# CANnode.net
KiCad netlist of a schematic drawn in Altium Designer
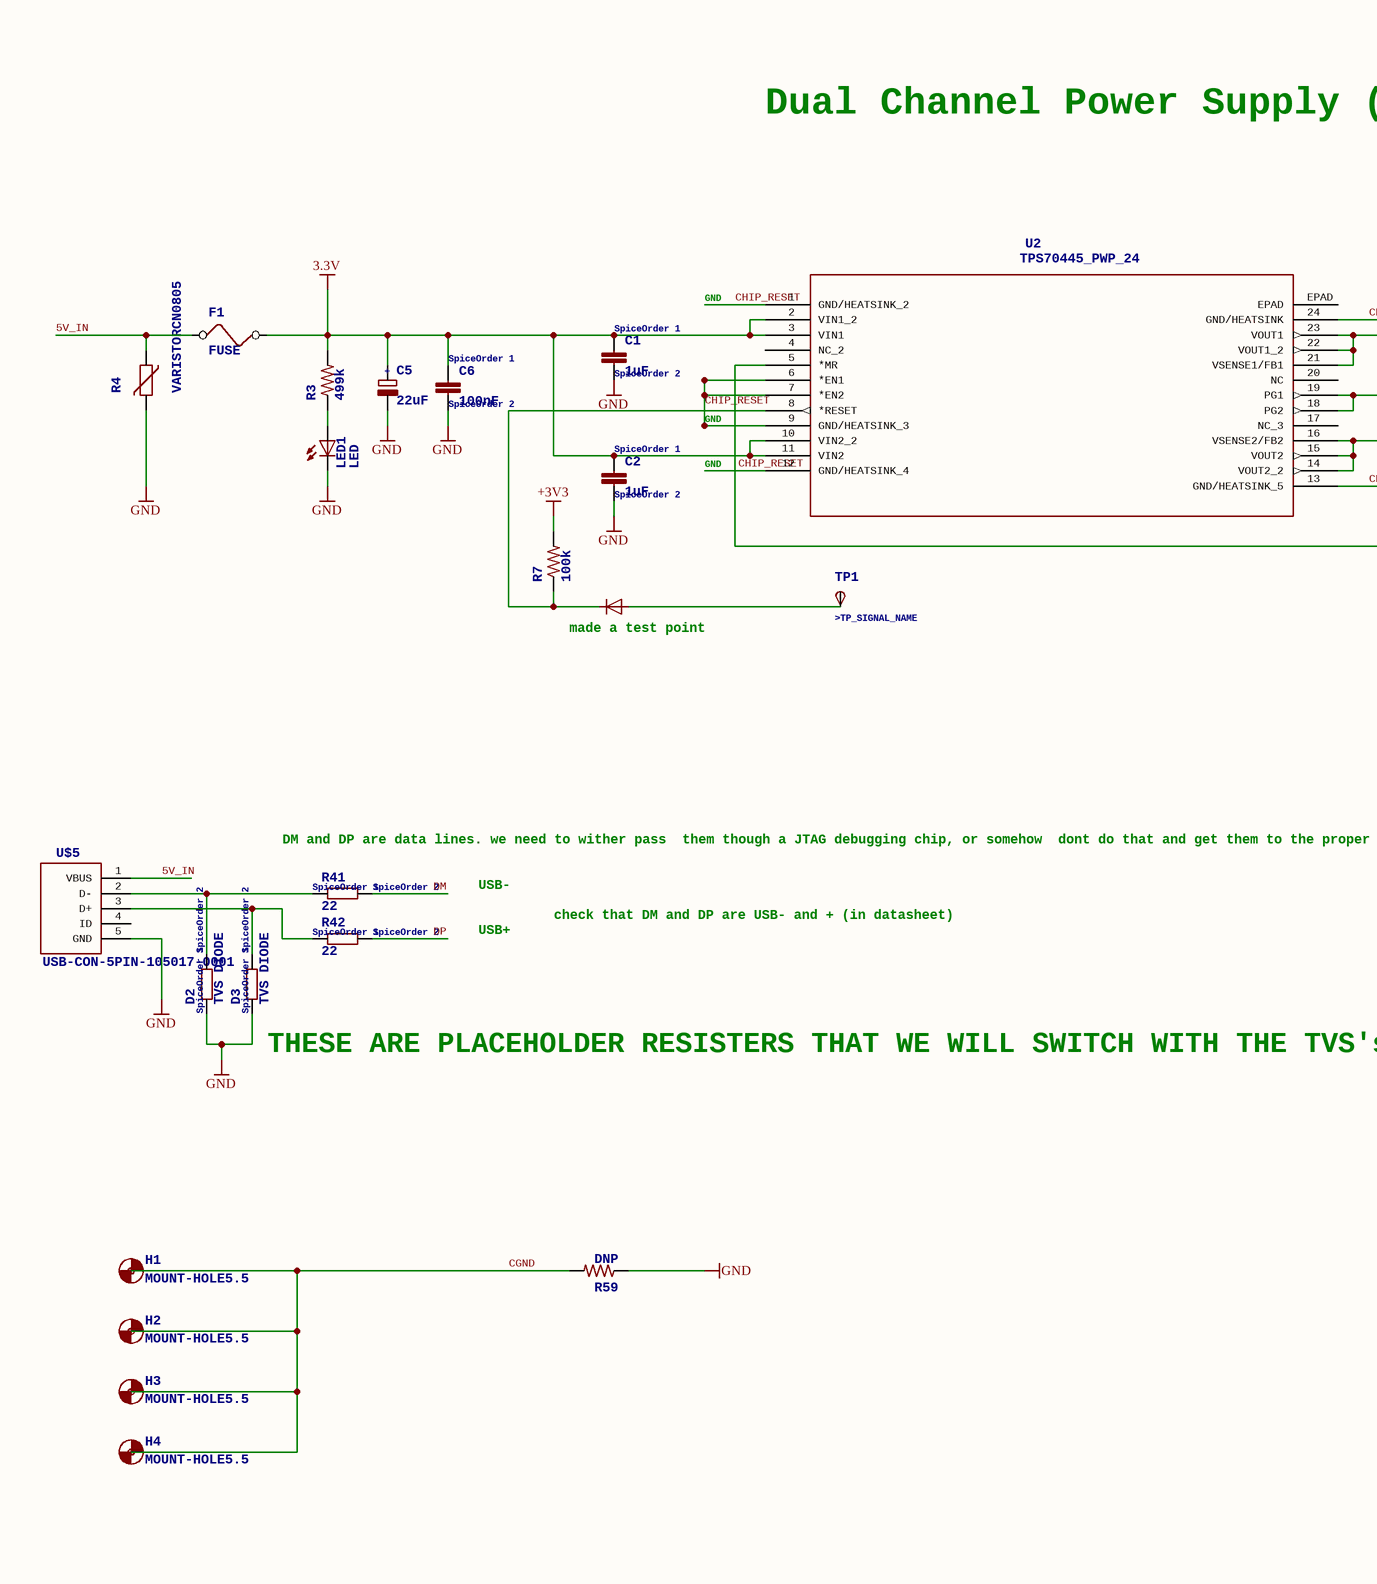
[diagram p0: CANnode.SchDoc, top left]
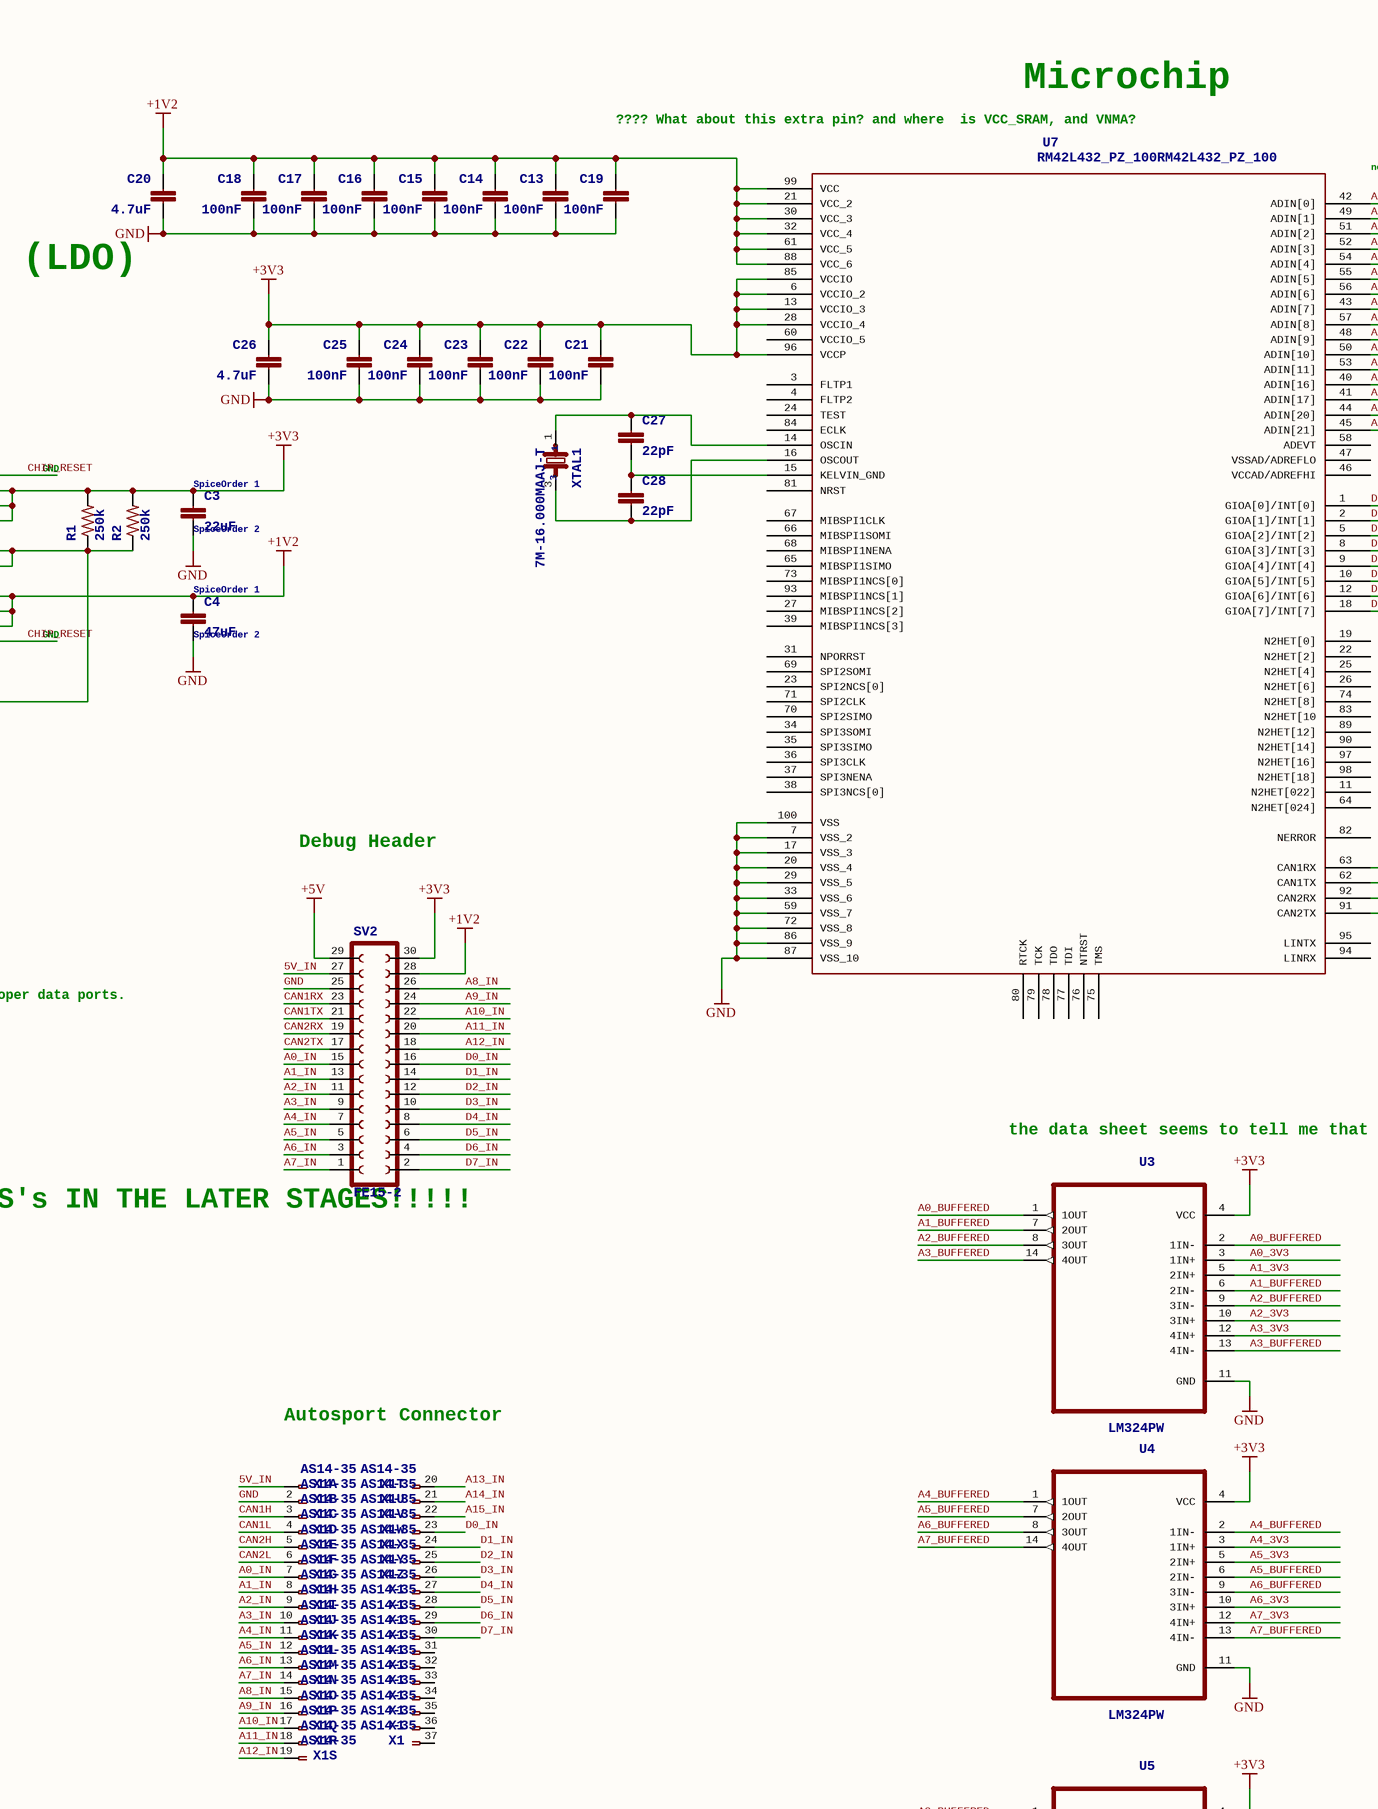
[diagram p1: CANnode.SchDoc, top middle]
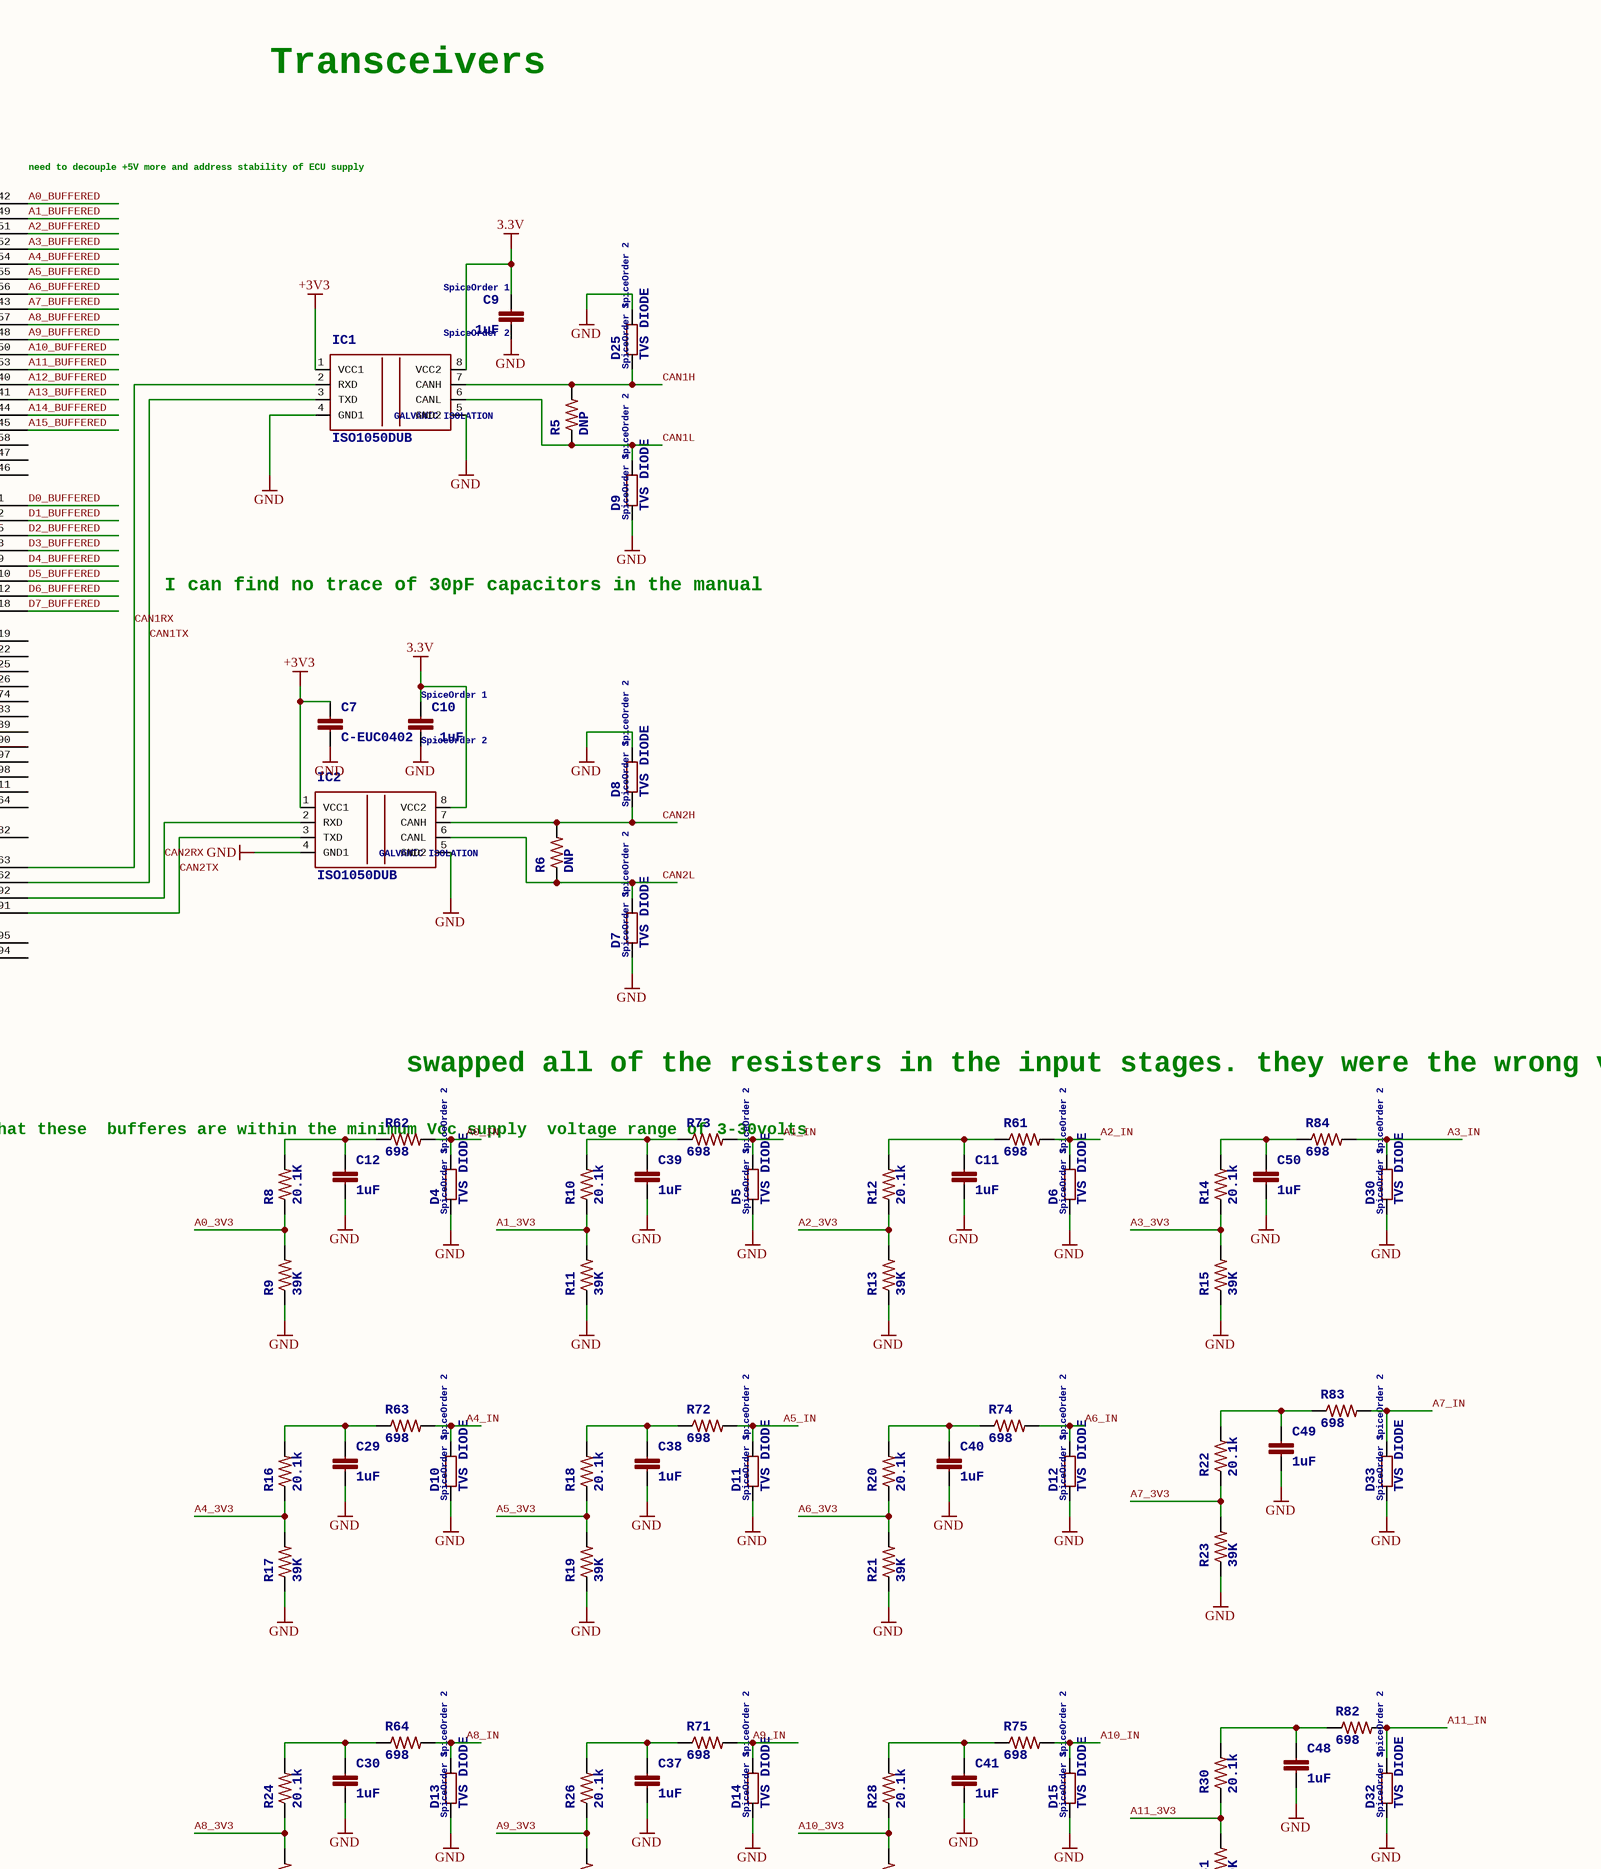
[diagram p2: CANnode.SchDoc, top right]
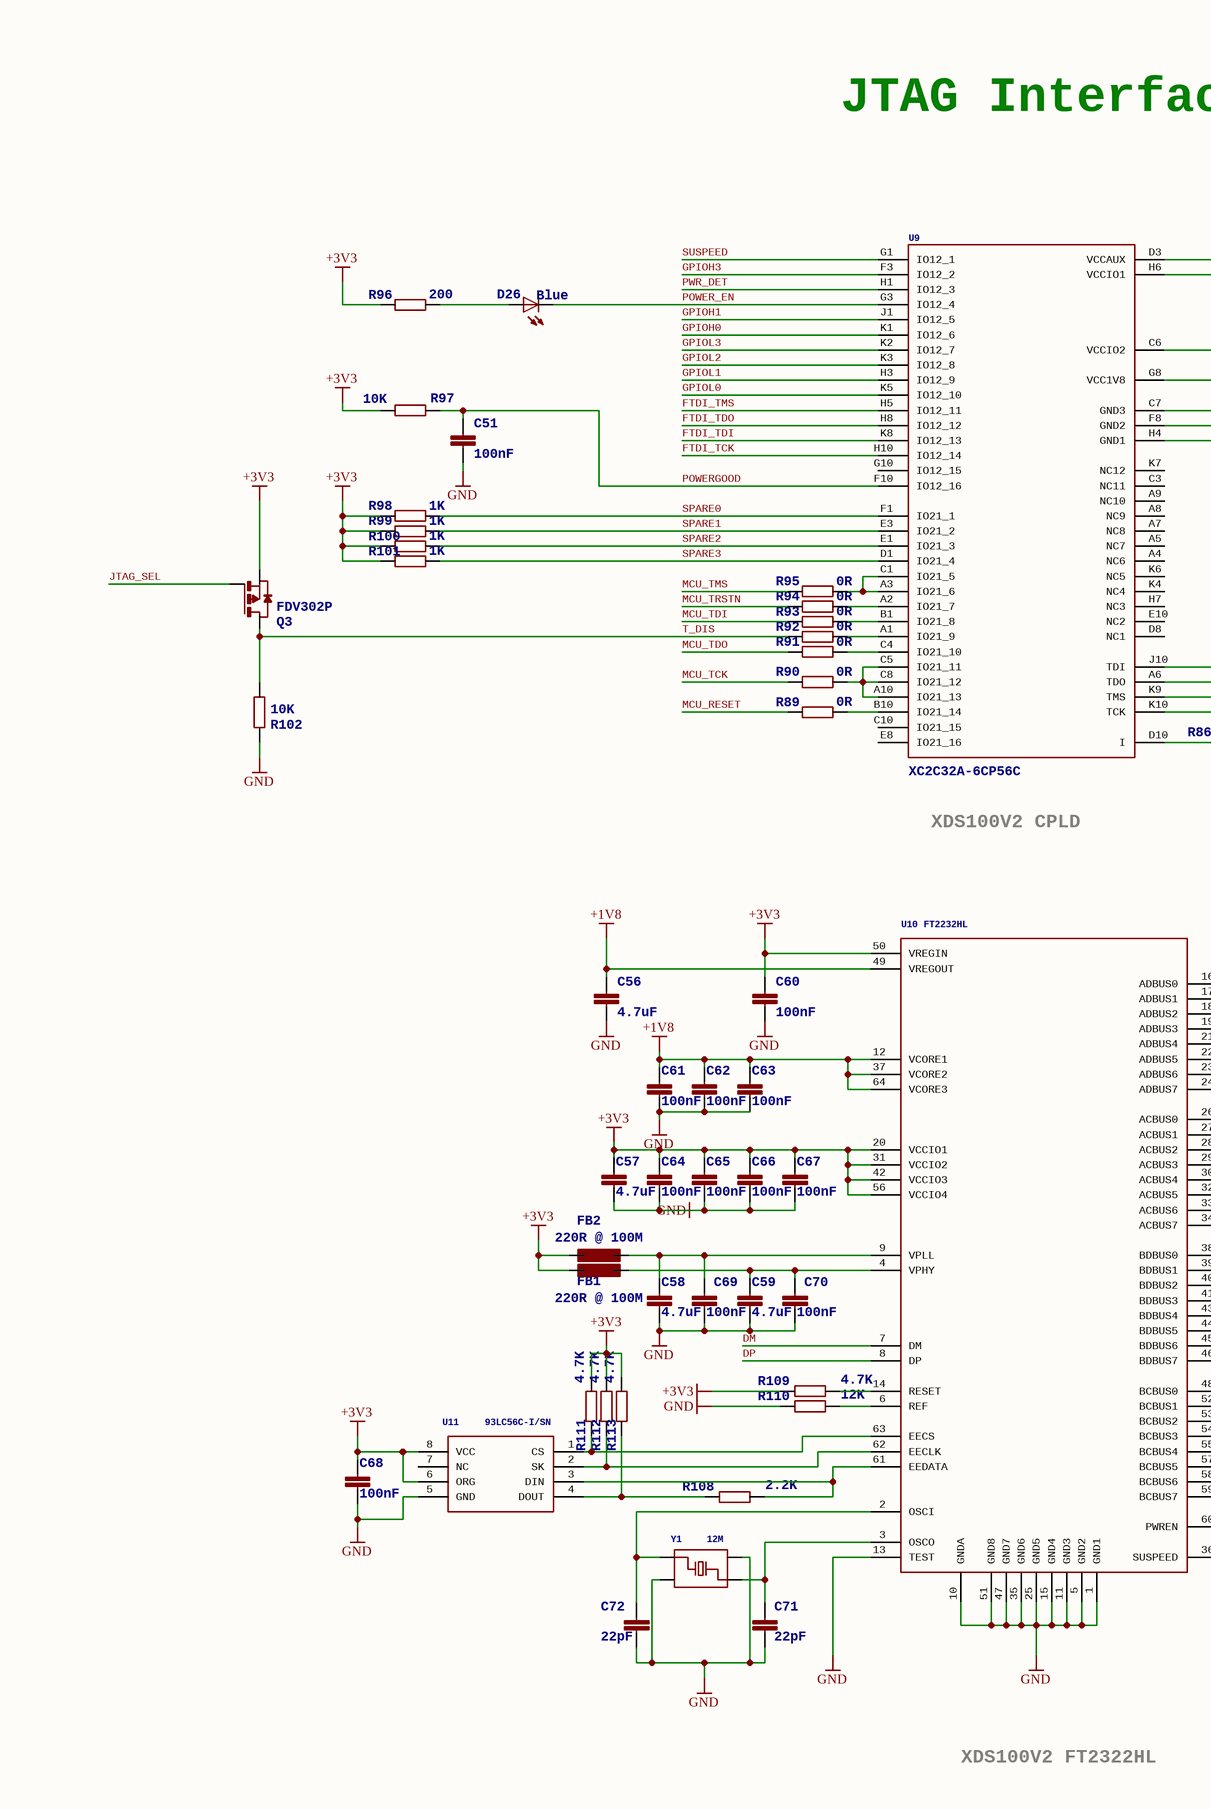
[diagram p3: CANnode.SchDoc, bottom left]
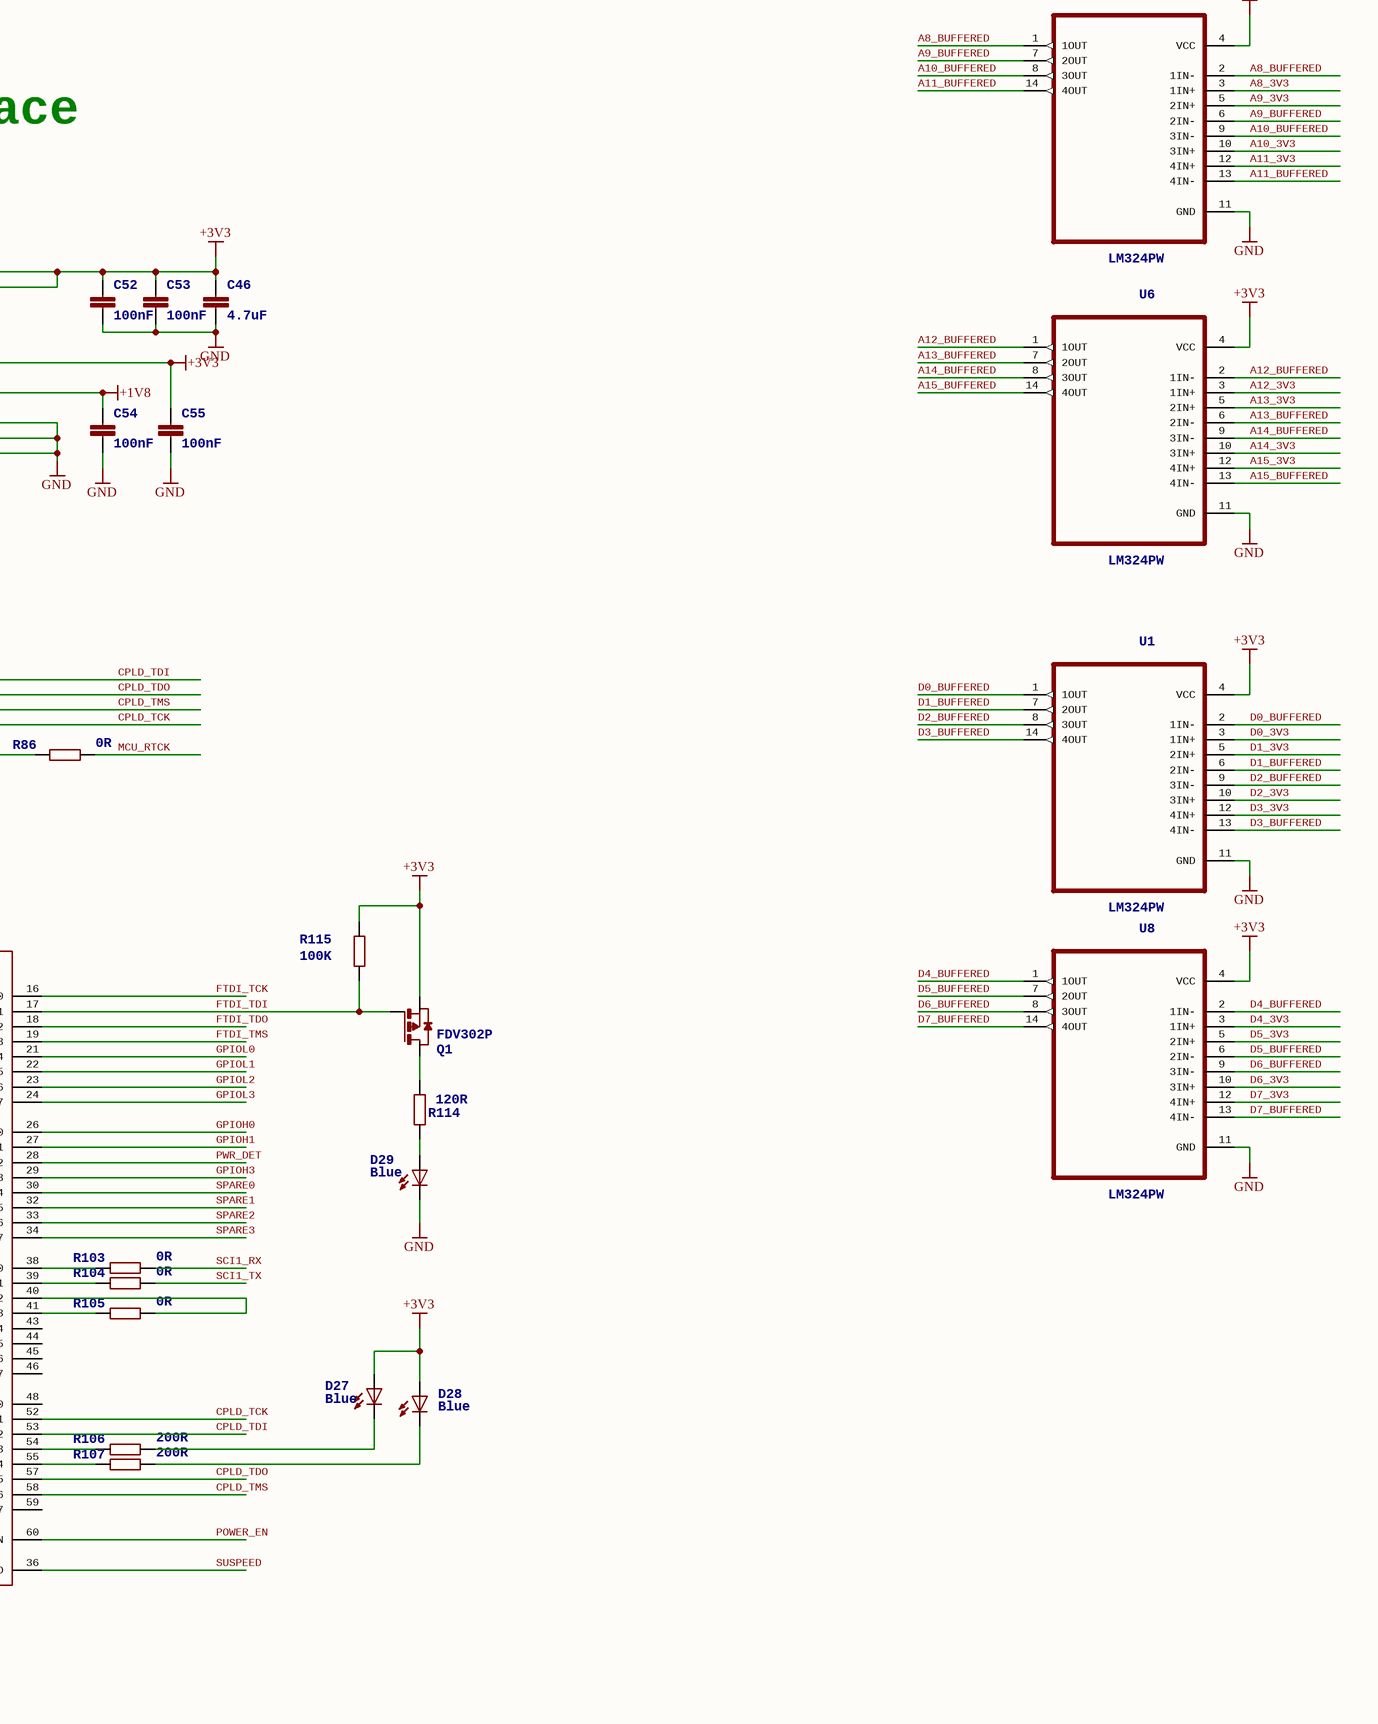
[diagram p4: CANnode.SchDoc, bottom middle]
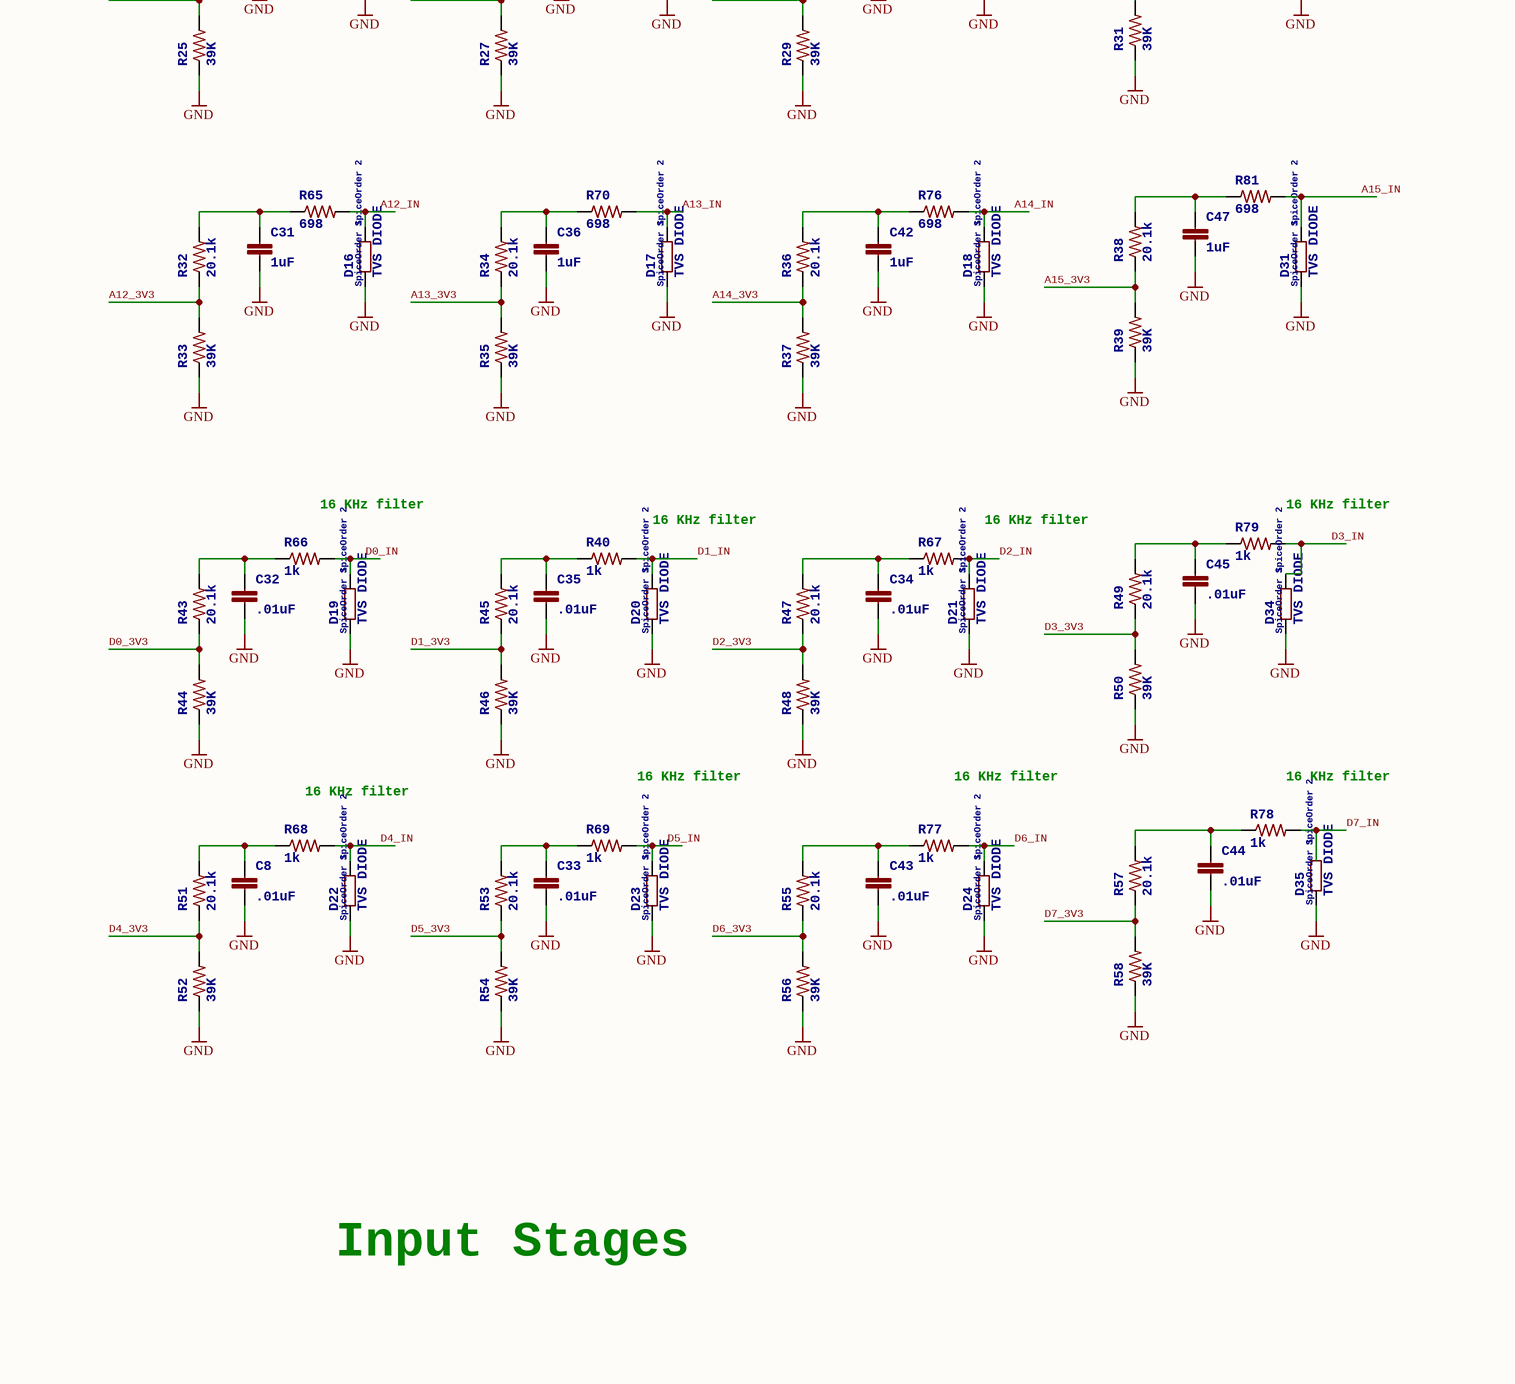
[diagram p5: CANnode.SchDoc, bottom right]

(export (version "E")
  (design (tool "Eeschema 10.0.6"))
  (components
    (comp (ref "C1")
      (value "1uF")
      (footprint "C0402")
      (description "<B>CAPACITOR</B>, European symbol")
      (fields (field (name "SPICEORDER 1") "SpiceOrder 1") (field (name "SPICEORDER 2") "SpiceOrder 2"))
      (libsource (lib "eagle-ltspice") (part "CC0402"))
    )
    (comp (ref "C2")
      (value "1uF")
      (footprint "C0402")
      (description "<B>CAPACITOR</B>, European symbol")
      (fields (field (name "SPICEORDER 1") "SpiceOrder 1") (field (name "SPICEORDER 2") "SpiceOrder 2"))
      (libsource (lib "eagle-ltspice") (part "CC0402"))
    )
    (comp (ref "C3")
      (value "22uF")
      (footprint "C0402")
      (description "<B>CAPACITOR</B>, European symbol")
      (fields (field (name "SPICEORDER 1") "SpiceOrder 1") (field (name "SPICEORDER 2") "SpiceOrder 2"))
      (libsource (lib "eagle-ltspice") (part "CC0402"))
    )
    (comp (ref "C4")
      (value "47uF")
      (footprint "C0402")
      (description "<B>CAPACITOR</B>, European symbol")
      (fields (field (name "SPICEORDER 1") "SpiceOrder 1") (field (name "SPICEORDER 2") "SpiceOrder 2"))
      (libsource (lib "eagle-ltspice") (part "CC0402"))
    )
    (comp (ref "C5")
      (value "22uF")
      (footprint "CT3528")
      (description "<B>POLARIZED CAPACITOR</B>, European symbol")
      (fields (field (name "+") "+"))
      (libsource (lib "resistor") (part "CPOL-EUCT3528"))
    )
    (comp (ref "C6")
      (value "100nF")
      (footprint "C0402")
      (description "<B>CAPACITOR</B>, European symbol")
      (fields (field (name "SPICEORDER 1") "SpiceOrder 1") (field (name "SPICEORDER 2") "SpiceOrder 2"))
      (libsource (lib "eagle-ltspice") (part "CC0402"))
    )
    (comp (ref "C7")
      (value "C-EUC0402")
      (footprint "C0402")
      (description "<B>CAPACITOR</B>, European symbol")
      (libsource (lib "") (part "C-EUC0402_1"))
    )
    (comp (ref "C8")
      (value ".01uF")
      (footprint "C0402")
      (description "<B>CAPACITOR</B>, European symbol")
      (libsource (lib "") (part "C-EUC0402_1"))
    )
    (comp (ref "C9")
      (value ".1uF")
      (footprint "C0402")
      (description "<B>CAPACITOR</B>, European symbol")
      (fields (field (name "SPICEORDER 1") "SpiceOrder 1") (field (name "SPICEORDER 2") "SpiceOrder 2"))
      (libsource (lib "") (part "CC0402_1"))
    )
    (comp (ref "C10")
      (value ".1uF")
      (footprint "C0402")
      (description "<B>CAPACITOR</B>, European symbol")
      (fields (field (name "SPICEORDER 1") "SpiceOrder 1") (field (name "SPICEORDER 2") "SpiceOrder 2"))
      (libsource (lib "eagle-ltspice") (part "CC0402"))
    )
    (comp (ref "C11")
      (value "1uF")
      (footprint "C0402")
      (description "<B>CAPACITOR</B>, European symbol")
      (libsource (lib "") (part "C-EUC0402_1"))
    )
    (comp (ref "C12")
      (value "1uF")
      (footprint "C0402")
      (description "<B>CAPACITOR</B>, European symbol")
      (libsource (lib "") (part "C-EUC0402_1"))
    )
    (comp (ref "C13")
      (value "100nF")
      (footprint "C0402")
      (description "<B>CAPACITOR</B>, European symbol")
      (libsource (lib "rcl") (part "C-EUC0402"))
    )
    (comp (ref "C14")
      (value "100nF")
      (footprint "C0402")
      (description "<B>CAPACITOR</B>, European symbol")
      (libsource (lib "rcl") (part "C-EUC0402"))
    )
    (comp (ref "C15")
      (value "100nF")
      (footprint "C0402")
      (description "<B>CAPACITOR</B>, European symbol")
      (libsource (lib "rcl") (part "C-EUC0402"))
    )
    (comp (ref "C16")
      (value "100nF")
      (footprint "C0402")
      (description "<B>CAPACITOR</B>, European symbol")
      (libsource (lib "rcl") (part "C-EUC0402"))
    )
    (comp (ref "C17")
      (value "100nF")
      (footprint "C0402")
      (description "<B>CAPACITOR</B>, European symbol")
      (libsource (lib "rcl") (part "C-EUC0402"))
    )
    (comp (ref "C18")
      (value "100nF")
      (footprint "C0402")
      (description "<B>CAPACITOR</B>, European symbol")
      (libsource (lib "rcl") (part "C-EUC0402"))
    )
    (comp (ref "C19")
      (value "100nF")
      (footprint "C0402")
      (description "<B>CAPACITOR</B>, European symbol")
      (libsource (lib "rcl") (part "C-EUC0402"))
    )
    (comp (ref "C20")
      (value "4.7uF")
      (footprint "C0805")
      (description "<B>CAPACITOR</B>, European symbol")
      (libsource (lib "rcl") (part "C-EUC0805"))
    )
    (comp (ref "C21")
      (value "100nF")
      (footprint "C0402")
      (description "<B>CAPACITOR</B>, European symbol")
      (libsource (lib "rcl") (part "C-EUC0402"))
    )
    (comp (ref "C22")
      (value "100nF")
      (footprint "C0402")
      (description "<B>CAPACITOR</B>, European symbol")
      (libsource (lib "rcl") (part "C-EUC0402"))
    )
    (comp (ref "C23")
      (value "100nF")
      (footprint "C0402")
      (description "<B>CAPACITOR</B>, European symbol")
      (libsource (lib "rcl") (part "C-EUC0402"))
    )
    (comp (ref "C24")
      (value "100nF")
      (footprint "C0402")
      (description "<B>CAPACITOR</B>, European symbol")
      (libsource (lib "rcl") (part "C-EUC0402"))
    )
    (comp (ref "C25")
      (value "100nF")
      (footprint "C0402")
      (description "<B>CAPACITOR</B>, European symbol")
      (libsource (lib "rcl") (part "C-EUC0402"))
    )
    (comp (ref "C26")
      (value "4.7uF")
      (footprint "C0805")
      (description "<B>CAPACITOR</B>, European symbol")
      (libsource (lib "rcl") (part "C-EUC0805"))
    )
    (comp (ref "C27")
      (value "22pF")
      (footprint "C0402")
      (description "<B>CAPACITOR</B>, European symbol")
      (libsource (lib "") (part "C-EUC0402_1"))
    )
    (comp (ref "C28")
      (value "22pF")
      (footprint "C0402")
      (description "<B>CAPACITOR</B>, European symbol")
      (libsource (lib "") (part "C-EUC0402_1"))
    )
    (comp (ref "C29")
      (value "1uF")
      (footprint "C0402")
      (description "<B>CAPACITOR</B>, European symbol")
      (libsource (lib "") (part "C-EUC0402_1"))
    )
    (comp (ref "C30")
      (value "1uF")
      (footprint "C0402")
      (description "<B>CAPACITOR</B>, European symbol")
      (libsource (lib "") (part "C-EUC0402_1"))
    )
    (comp (ref "C31")
      (value "1uF")
      (footprint "C0402")
      (description "<B>CAPACITOR</B>, European symbol")
      (libsource (lib "") (part "C-EUC0402_1"))
    )
    (comp (ref "C32")
      (value ".01uF")
      (footprint "C0402")
      (description "<B>CAPACITOR</B>, European symbol")
      (libsource (lib "") (part "C-EUC0402_1"))
    )
    (comp (ref "C33")
      (value ".01uF")
      (footprint "C0402")
      (description "<B>CAPACITOR</B>, European symbol")
      (libsource (lib "") (part "C-EUC0402_1"))
    )
    (comp (ref "C34")
      (value ".01uF")
      (footprint "C0402")
      (description "<B>CAPACITOR</B>, European symbol")
      (libsource (lib "") (part "C-EUC0402_1"))
    )
    (comp (ref "C35")
      (value ".01uF")
      (footprint "C0402")
      (description "<B>CAPACITOR</B>, European symbol")
      (libsource (lib "") (part "C-EUC0402_1"))
    )
    (comp (ref "C36")
      (value "1uF")
      (footprint "C0402")
      (description "<B>CAPACITOR</B>, European symbol")
      (libsource (lib "") (part "C-EUC0402_1"))
    )
    (comp (ref "C37")
      (value "1uF")
      (footprint "C0402")
      (description "<B>CAPACITOR</B>, European symbol")
      (libsource (lib "") (part "C-EUC0402_1"))
    )
    (comp (ref "C38")
      (value "1uF")
      (footprint "C0402")
      (description "<B>CAPACITOR</B>, European symbol")
      (libsource (lib "") (part "C-EUC0402_1"))
    )
    (comp (ref "C39")
      (value "1uF")
      (footprint "C0402")
      (description "<B>CAPACITOR</B>, European symbol")
      (libsource (lib "") (part "C-EUC0402_1"))
    )
    (comp (ref "C40")
      (value "1uF")
      (footprint "C0402")
      (description "<B>CAPACITOR</B>, European symbol")
      (libsource (lib "") (part "C-EUC0402_1"))
    )
    (comp (ref "C41")
      (value "1uF")
      (footprint "C0402")
      (description "<B>CAPACITOR</B>, European symbol")
      (libsource (lib "") (part "C-EUC0402_1"))
    )
    (comp (ref "C42")
      (value "1uF")
      (footprint "C0402")
      (description "<B>CAPACITOR</B>, European symbol")
      (libsource (lib "") (part "C-EUC0402_1"))
    )
    (comp (ref "C43")
      (value ".01uF")
      (footprint "C0402")
      (description "<B>CAPACITOR</B>, European symbol")
      (libsource (lib "") (part "C-EUC0402_1"))
    )
    (comp (ref "C44")
      (value ".01uF")
      (footprint "C0402")
      (description "<B>CAPACITOR</B>, European symbol")
      (libsource (lib "") (part "C-EUC0402_1"))
    )
    (comp (ref "C45")
      (value ".01uF")
      (footprint "C0402")
      (description "<B>CAPACITOR</B>, European symbol")
      (libsource (lib "") (part "C-EUC0402_1"))
    )
    (comp (ref "C46") (value "4.7uF") (footprint "0805") (libsource (lib "launchpad") (part "CAP0805")))
    (comp (ref "C47")
      (value "1uF")
      (footprint "C0402")
      (description "<B>CAPACITOR</B>, European symbol")
      (libsource (lib "") (part "C-EUC0402_1"))
    )
    (comp (ref "C48")
      (value "1uF")
      (footprint "C0402")
      (description "<B>CAPACITOR</B>, European symbol")
      (libsource (lib "") (part "C-EUC0402_1"))
    )
    (comp (ref "C49")
      (value "1uF")
      (footprint "C0402")
      (description "<B>CAPACITOR</B>, European symbol")
      (libsource (lib "") (part "C-EUC0402_1"))
    )
    (comp (ref "C50")
      (value "1uF")
      (footprint "C0402")
      (description "<B>CAPACITOR</B>, European symbol")
      (libsource (lib "") (part "C-EUC0402_1"))
    )
    (comp (ref "C51") (value "100nF") (footprint "0402") (libsource (lib "launchpad") (part "CAP0402")))
    (comp (ref "C52") (value "100nF") (footprint "0402") (libsource (lib "launchpad") (part "CAP0402")))
    (comp (ref "C53") (value "100nF") (footprint "0402") (libsource (lib "launchpad") (part "CAP0402")))
    (comp (ref "C54") (value "100nF") (footprint "0402") (libsource (lib "launchpad") (part "CAP0402")))
    (comp (ref "C55") (value "100nF") (footprint "0402") (libsource (lib "launchpad") (part "CAP0402")))
    (comp (ref "C56") (value "4.7uF") (footprint "0805") (libsource (lib "launchpad") (part "CAP0805")))
    (comp (ref "C57") (value "4.7uF") (footprint "0805") (libsource (lib "launchpad") (part "CAP0805")))
    (comp (ref "C58") (value "4.7uF") (footprint "0805") (libsource (lib "launchpad") (part "CAP0805")))
    (comp (ref "C59") (value "4.7uF") (footprint "0805") (libsource (lib "launchpad") (part "CAP0805")))
    (comp (ref "C60") (value "100nF") (footprint "0402") (libsource (lib "launchpad") (part "CAP0402")))
    (comp (ref "C61") (value "100nF") (footprint "0402") (libsource (lib "launchpad") (part "CAP0402")))
    (comp (ref "C62") (value "100nF") (footprint "0402") (libsource (lib "launchpad") (part "CAP0402")))
    (comp (ref "C63") (value "100nF") (footprint "0402") (libsource (lib "launchpad") (part "CAP0402")))
    (comp (ref "C64") (value "100nF") (footprint "0402") (libsource (lib "launchpad") (part "CAP0402")))
    (comp (ref "C65") (value "100nF") (footprint "0402") (libsource (lib "launchpad") (part "CAP0402")))
    (comp (ref "C66") (value "100nF") (footprint "0402") (libsource (lib "launchpad") (part "CAP0402")))
    (comp (ref "C67") (value "100nF") (footprint "0402") (libsource (lib "launchpad") (part "CAP0402")))
    (comp (ref "C68") (value "100nF") (footprint "0402") (libsource (lib "launchpad") (part "CAP0402")))
    (comp (ref "C69") (value "100nF") (footprint "0402") (libsource (lib "launchpad") (part "CAP0402")))
    (comp (ref "C70") (value "100nF") (footprint "0402") (libsource (lib "launchpad") (part "CAP0402")))
    (comp (ref "C71") (value "22pF") (footprint "0402") (libsource (lib "launchpad") (part "CAP0402")))
    (comp (ref "C72") (value "22pF") (footprint "0402") (libsource (lib "launchpad") (part "CAP0402")))
    (comp (ref "D1")
      (value "DIODE")
      (description "<B>DIODE</B><p>")
      (libsource (lib "docu-dummy") (part "DIODE"))
    )
    (comp (ref "D2")
      (value "TVS DIODE")
      (footprint "R0402")
      (description "<B>RESISTOR</B>, European symbol")
      (fields (field (name "SPICEORDER 1") "SpiceOrder 1") (field (name "SPICEORDER 2") "SpiceOrder 2"))
      (libsource (lib "eagle-ltspice") (part "RR0402"))
    )
    (comp (ref "D3")
      (value "TVS DIODE")
      (footprint "R0402")
      (description "<B>RESISTOR</B>, European symbol")
      (fields (field (name "SPICEORDER 1") "SpiceOrder 1") (field (name "SPICEORDER 2") "SpiceOrder 2"))
      (libsource (lib "eagle-ltspice") (part "RR0402"))
    )
    (comp (ref "D4")
      (value "TVS DIODE")
      (footprint "R0402")
      (description "<B>RESISTOR</B>, European symbol")
      (fields (field (name "SPICEORDER 1") "SpiceOrder 1") (field (name "SPICEORDER 2") "SpiceOrder 2"))
      (libsource (lib "eagle-ltspice") (part "RR0402"))
    )
    (comp (ref "D5")
      (value "TVS DIODE")
      (footprint "R0402")
      (description "<B>RESISTOR</B>, European symbol")
      (fields (field (name "SPICEORDER 1") "SpiceOrder 1") (field (name "SPICEORDER 2") "SpiceOrder 2"))
      (libsource (lib "eagle-ltspice") (part "RR0402"))
    )
    (comp (ref "D6")
      (value "TVS DIODE")
      (footprint "R0402")
      (description "<B>RESISTOR</B>, European symbol")
      (fields (field (name "SPICEORDER 1") "SpiceOrder 1") (field (name "SPICEORDER 2") "SpiceOrder 2"))
      (libsource (lib "eagle-ltspice") (part "RR0402"))
    )
    (comp (ref "D7")
      (value "TVS DIODE")
      (footprint "R0402")
      (description "<B>RESISTOR</B>, European symbol")
      (fields (field (name "SPICEORDER 1") "SpiceOrder 1") (field (name "SPICEORDER 2") "SpiceOrder 2"))
      (libsource (lib "eagle-ltspice") (part "RR0402"))
    )
    (comp (ref "D8")
      (value "TVS DIODE")
      (footprint "R0402")
      (description "<B>RESISTOR</B>, European symbol")
      (fields (field (name "SPICEORDER 1") "SpiceOrder 1") (field (name "SPICEORDER 2") "SpiceOrder 2"))
      (libsource (lib "eagle-ltspice") (part "RR0402"))
    )
    (comp (ref "D9")
      (value "TVS DIODE")
      (footprint "R0402")
      (description "<B>RESISTOR</B>, European symbol")
      (fields (field (name "SPICEORDER 1") "SpiceOrder 1") (field (name "SPICEORDER 2") "SpiceOrder 2"))
      (libsource (lib "eagle-ltspice") (part "RR0402"))
    )
    (comp (ref "D10")
      (value "TVS DIODE")
      (footprint "R0402")
      (description "<B>RESISTOR</B>, European symbol")
      (fields (field (name "SPICEORDER 1") "SpiceOrder 1") (field (name "SPICEORDER 2") "SpiceOrder 2"))
      (libsource (lib "eagle-ltspice") (part "RR0402"))
    )
    (comp (ref "D11")
      (value "TVS DIODE")
      (footprint "R0402")
      (description "<B>RESISTOR</B>, European symbol")
      (fields (field (name "SPICEORDER 1") "SpiceOrder 1") (field (name "SPICEORDER 2") "SpiceOrder 2"))
      (libsource (lib "eagle-ltspice") (part "RR0402"))
    )
    (comp (ref "D12")
      (value "TVS DIODE")
      (footprint "R0402")
      (description "<B>RESISTOR</B>, European symbol")
      (fields (field (name "SPICEORDER 1") "SpiceOrder 1") (field (name "SPICEORDER 2") "SpiceOrder 2"))
      (libsource (lib "eagle-ltspice") (part "RR0402"))
    )
    (comp (ref "D13")
      (value "TVS DIODE")
      (footprint "R0402")
      (description "<B>RESISTOR</B>, European symbol")
      (fields (field (name "SPICEORDER 1") "SpiceOrder 1") (field (name "SPICEORDER 2") "SpiceOrder 2"))
      (libsource (lib "eagle-ltspice") (part "RR0402"))
    )
    (comp (ref "D14")
      (value "TVS DIODE")
      (footprint "R0402")
      (description "<B>RESISTOR</B>, European symbol")
      (fields (field (name "SPICEORDER 1") "SpiceOrder 1") (field (name "SPICEORDER 2") "SpiceOrder 2"))
      (libsource (lib "eagle-ltspice") (part "RR0402"))
    )
    (comp (ref "D15")
      (value "TVS DIODE")
      (footprint "R0402")
      (description "<B>RESISTOR</B>, European symbol")
      (fields (field (name "SPICEORDER 1") "SpiceOrder 1") (field (name "SPICEORDER 2") "SpiceOrder 2"))
      (libsource (lib "eagle-ltspice") (part "RR0402"))
    )
    (comp (ref "D16")
      (value "TVS DIODE")
      (footprint "R0402")
      (description "<B>RESISTOR</B>, European symbol")
      (fields (field (name "SPICEORDER 1") "SpiceOrder 1") (field (name "SPICEORDER 2") "SpiceOrder 2"))
      (libsource (lib "eagle-ltspice") (part "RR0402"))
    )
    (comp (ref "D17")
      (value "TVS DIODE")
      (footprint "R0402")
      (description "<B>RESISTOR</B>, European symbol")
      (fields (field (name "SPICEORDER 1") "SpiceOrder 1") (field (name "SPICEORDER 2") "SpiceOrder 2"))
      (libsource (lib "eagle-ltspice") (part "RR0402"))
    )
    (comp (ref "D18")
      (value "TVS DIODE")
      (footprint "R0402")
      (description "<B>RESISTOR</B>, European symbol")
      (fields (field (name "SPICEORDER 1") "SpiceOrder 1") (field (name "SPICEORDER 2") "SpiceOrder 2"))
      (libsource (lib "eagle-ltspice") (part "RR0402"))
    )
    (comp (ref "D19")
      (value "TVS DIODE")
      (footprint "R0402")
      (description "<B>RESISTOR</B>, European symbol")
      (fields (field (name "SPICEORDER 1") "SpiceOrder 1") (field (name "SPICEORDER 2") "SpiceOrder 2"))
      (libsource (lib "eagle-ltspice") (part "RR0402"))
    )
    (comp (ref "D20")
      (value "TVS DIODE")
      (footprint "R0402")
      (description "<B>RESISTOR</B>, European symbol")
      (fields (field (name "SPICEORDER 1") "SpiceOrder 1") (field (name "SPICEORDER 2") "SpiceOrder 2"))
      (libsource (lib "eagle-ltspice") (part "RR0402"))
    )
    (comp (ref "D21")
      (value "TVS DIODE")
      (footprint "R0402")
      (description "<B>RESISTOR</B>, European symbol")
      (fields (field (name "SPICEORDER 1") "SpiceOrder 1") (field (name "SPICEORDER 2") "SpiceOrder 2"))
      (libsource (lib "eagle-ltspice") (part "RR0402"))
    )
    (comp (ref "D22")
      (value "TVS DIODE")
      (footprint "R0402")
      (description "<B>RESISTOR</B>, European symbol")
      (fields (field (name "SPICEORDER 1") "SpiceOrder 1") (field (name "SPICEORDER 2") "SpiceOrder 2"))
      (libsource (lib "eagle-ltspice") (part "RR0402"))
    )
    (comp (ref "D23")
      (value "TVS DIODE")
      (footprint "R0402")
      (description "<B>RESISTOR</B>, European symbol")
      (fields (field (name "SPICEORDER 1") "SpiceOrder 1") (field (name "SPICEORDER 2") "SpiceOrder 2"))
      (libsource (lib "eagle-ltspice") (part "RR0402"))
    )
    (comp (ref "D24")
      (value "TVS DIODE")
      (footprint "R0402")
      (description "<B>RESISTOR</B>, European symbol")
      (fields (field (name "SPICEORDER 1") "SpiceOrder 1") (field (name "SPICEORDER 2") "SpiceOrder 2"))
      (libsource (lib "eagle-ltspice") (part "RR0402"))
    )
    (comp (ref "D25")
      (value "TVS DIODE")
      (footprint "R0402")
      (description "<B>RESISTOR</B>, European symbol")
      (fields (field (name "SPICEORDER 1") "SpiceOrder 1") (field (name "SPICEORDER 2") "SpiceOrder 2"))
      (libsource (lib "eagle-ltspice") (part "RR0402"))
    )
    (comp (ref "D26") (value "Blue") (footprint "LED0805") (libsource (lib "launchpad") (part "CHIP-LED")))
    (comp (ref "D27") (value "Blue") (footprint "LED0805") (libsource (lib "launchpad") (part "CHIP-LED")))
    (comp (ref "D28") (value "Blue") (footprint "LED0805") (libsource (lib "launchpad") (part "CHIP-LED")))
    (comp (ref "D29") (value "Blue") (footprint "LED0805") (libsource (lib "launchpad") (part "CHIP-LED")))
    (comp (ref "D30")
      (value "TVS DIODE")
      (footprint "R0402")
      (description "<B>RESISTOR</B>, European symbol")
      (fields (field (name "SPICEORDER 1") "SpiceOrder 1") (field (name "SPICEORDER 2") "SpiceOrder 2"))
      (libsource (lib "eagle-ltspice") (part "RR0402"))
    )
    (comp (ref "D31")
      (value "TVS DIODE")
      (footprint "R0402")
      (description "<B>RESISTOR</B>, European symbol")
      (fields (field (name "SPICEORDER 1") "SpiceOrder 1") (field (name "SPICEORDER 2") "SpiceOrder 2"))
      (libsource (lib "eagle-ltspice") (part "RR0402"))
    )
    (comp (ref "D32")
      (value "TVS DIODE")
      (footprint "R0402")
      (description "<B>RESISTOR</B>, European symbol")
      (fields (field (name "SPICEORDER 1") "SpiceOrder 1") (field (name "SPICEORDER 2") "SpiceOrder 2"))
      (libsource (lib "eagle-ltspice") (part "RR0402"))
    )
    (comp (ref "D33")
      (value "TVS DIODE")
      (footprint "R0402")
      (description "<B>RESISTOR</B>, European symbol")
      (fields (field (name "SPICEORDER 1") "SpiceOrder 1") (field (name "SPICEORDER 2") "SpiceOrder 2"))
      (libsource (lib "eagle-ltspice") (part "RR0402"))
    )
    (comp (ref "D34")
      (value "TVS DIODE")
      (footprint "R0402")
      (description "<B>RESISTOR</B>, European symbol")
      (fields (field (name "SPICEORDER 1") "SpiceOrder 1") (field (name "SPICEORDER 2") "SpiceOrder 2"))
      (libsource (lib "eagle-ltspice") (part "RR0402"))
    )
    (comp (ref "D35")
      (value "TVS DIODE")
      (footprint "R0402")
      (description "<B>RESISTOR</B>, European symbol")
      (fields (field (name "SPICEORDER 1") "SpiceOrder 1") (field (name "SPICEORDER 2") "SpiceOrder 2"))
      (libsource (lib "eagle-ltspice") (part "RR0402"))
    )
    (comp (ref "F1")
      (value "FUSE")
      (footprint "FUSE")
      (description "<B>FUSE</B><p>\n5 x 20 mm")
      (libsource (lib "special") (part "FUSE"))
    )
    (comp (ref "FB1")
      (value "220R @ 100M")
      (footprint "0805")
      (libsource (lib "launchpad") (part "INDUCTOR"))
    )
    (comp (ref "FB2")
      (value "220R @ 100M")
      (footprint "0805")
      (libsource (lib "launchpad") (part "INDUCTOR"))
    )
    (comp (ref "H1")
      (value "MOUNT-HOLE5.5")
      (footprint "5,5")
      (description "<b>MOUNTING HOLE</b> with drill center marker")
      (libsource (lib "holes") (part "MOUNT-HOLE5.5"))
    )
    (comp (ref "H2")
      (value "MOUNT-HOLE5.5")
      (footprint "5,5")
      (description "<b>MOUNTING HOLE</b> with drill center marker")
      (libsource (lib "holes") (part "MOUNT-HOLE5.5"))
    )
    (comp (ref "H3")
      (value "MOUNT-HOLE5.5")
      (footprint "5,5")
      (description "<b>MOUNTING HOLE</b> with drill center marker")
      (libsource (lib "holes") (part "MOUNT-HOLE5.5"))
    )
    (comp (ref "H4")
      (value "MOUNT-HOLE5.5")
      (footprint "5,5")
      (description "<b>MOUNTING HOLE</b> with drill center marker")
      (libsource (lib "holes") (part "MOUNT-HOLE5.5"))
    )
    (comp (ref "IC1")
      (value "ISO1050DUB")
      (footprint "DUB-R-PDSO-G8")
      (description "<b>ISOLATED CAN TRANSCEIVER</b><p>\nSource: http://focus.ti.com/lit/ds/symlink/iso1050.pdf")
      (fields (field (name "MPN") "ISO1050DUBR") (field (name "GALVANIC ISOLATION") "GALVANIC ISOLATION"))
      (libsource (lib "texas") (part "ISO1050DUB"))
    )
    (comp (ref "IC2")
      (value "ISO1050DUB")
      (footprint "DUB-R-PDSO-G8")
      (description "<b>ISOLATED CAN TRANSCEIVER</b><p>\nSource: http://focus.ti.com/lit/ds/symlink/iso1050.pdf")
      (fields (field (name "MPN") "ISO1050DUBR") (field (name "GALVANIC ISOLATION") "GALVANIC ISOLATION"))
      (libsource (lib "texas") (part "ISO1050DUB"))
    )
    (comp (ref "LED1") (value "LED") (footprint "SMARTLED-TTW") (libsource (lib "led") (part "LED")))
    (comp (ref "Q1")
      (value "FDV302P")
      (footprint "SOT-23")
      (description "<b>MOS FET</b>")
      (libsource (lib "zetex") (part "PMOSSOT23"))
    )
    (comp (ref "Q3")
      (value "FDV302P")
      (footprint "SOT-23")
      (description "<b>MOS FET</b>")
      (libsource (lib "zetex") (part "PMOSSOT23"))
    )
    (comp (ref "R1")
      (value "250k")
      (footprint "R0402")
      (description "<B>RESISTOR</B>, American symbol")
      (libsource (lib "resistor") (part "R-US_R0402"))
    )
    (comp (ref "R2")
      (value "250k")
      (footprint "R0402")
      (description "<B>RESISTOR</B>, American symbol")
      (libsource (lib "resistor") (part "R-US_R0402"))
    )
    (comp (ref "R3")
      (value "499k")
      (footprint "R0402")
      (description "<B>RESISTOR</B>, American symbol")
      (libsource (lib "resistor") (part "R-US_R0402"))
    )
    (comp (ref "R4")
      (value "VARISTORCN0805")
      (footprint "CT/CN0805")
      (description "<b>VARISTOR</b>")
      (libsource (lib "varistor") (part "VARISTORCN0805"))
    )
    (comp (ref "R5")
      (value "DNP")
      (footprint "R0402")
      (description "<B>RESISTOR</B>, American symbol")
      (libsource (lib "resistor") (part "R-US_R0402"))
    )
    (comp (ref "R6")
      (value "DNP")
      (footprint "R0402")
      (description "<B>RESISTOR</B>, American symbol")
      (libsource (lib "resistor") (part "R-US_R0402"))
    )
    (comp (ref "R7")
      (value "100k")
      (footprint "R0402")
      (description "<B>RESISTOR</B>, American symbol")
      (libsource (lib "resistor") (part "R-US_R0402"))
    )
    (comp (ref "R8")
      (value "20.1K")
      (footprint "R0402")
      (description "<B>RESISTOR</B>, American symbol")
      (libsource (lib "resistor") (part "R-US_R0402"))
    )
    (comp (ref "R9")
      (value "39K")
      (footprint "R0402")
      (description "<B>RESISTOR</B>, American symbol")
      (libsource (lib "resistor") (part "R-US_R0402"))
    )
    (comp (ref "R10")
      (value "20.1k")
      (footprint "R0402")
      (description "<B>RESISTOR</B>, American symbol")
      (libsource (lib "resistor") (part "R-US_R0402"))
    )
    (comp (ref "R11")
      (value "39K")
      (footprint "R0402")
      (description "<B>RESISTOR</B>, American symbol")
      (libsource (lib "resistor") (part "R-US_R0402"))
    )
    (comp (ref "R12")
      (value "20.1k")
      (footprint "R0402")
      (description "<B>RESISTOR</B>, American symbol")
      (libsource (lib "resistor") (part "R-US_R0402"))
    )
    (comp (ref "R13")
      (value "39K")
      (footprint "R0402")
      (description "<B>RESISTOR</B>, American symbol")
      (libsource (lib "resistor") (part "R-US_R0402"))
    )
    (comp (ref "R14")
      (value "20.1k")
      (footprint "R0402")
      (description "<B>RESISTOR</B>, American symbol")
      (libsource (lib "resistor") (part "R-US_R0402"))
    )
    (comp (ref "R15")
      (value "39K")
      (footprint "R0402")
      (description "<B>RESISTOR</B>, American symbol")
      (libsource (lib "resistor") (part "R-US_R0402"))
    )
    (comp (ref "R16")
      (value "20.1k")
      (footprint "R0402")
      (description "<B>RESISTOR</B>, American symbol")
      (libsource (lib "resistor") (part "R-US_R0402"))
    )
    (comp (ref "R17")
      (value "39K")
      (footprint "R0402")
      (description "<B>RESISTOR</B>, American symbol")
      (libsource (lib "resistor") (part "R-US_R0402"))
    )
    (comp (ref "R18")
      (value "20.1k")
      (footprint "R0402")
      (description "<B>RESISTOR</B>, American symbol")
      (libsource (lib "resistor") (part "R-US_R0402"))
    )
    (comp (ref "R19")
      (value "39K")
      (footprint "R0402")
      (description "<B>RESISTOR</B>, American symbol")
      (libsource (lib "resistor") (part "R-US_R0402"))
    )
    (comp (ref "R20")
      (value "20.1k")
      (footprint "R0402")
      (description "<B>RESISTOR</B>, American symbol")
      (libsource (lib "resistor") (part "R-US_R0402"))
    )
    (comp (ref "R21")
      (value "39K")
      (footprint "R0402")
      (description "<B>RESISTOR</B>, American symbol")
      (libsource (lib "resistor") (part "R-US_R0402"))
    )
    (comp (ref "R22")
      (value "20.1k")
      (footprint "R0402")
      (description "<B>RESISTOR</B>, American symbol")
      (libsource (lib "resistor") (part "R-US_R0402"))
    )
    (comp (ref "R23")
      (value "39K")
      (footprint "R0402")
      (description "<B>RESISTOR</B>, American symbol")
      (libsource (lib "resistor") (part "R-US_R0402"))
    )
    (comp (ref "R24")
      (value "20.1k")
      (footprint "R0402")
      (description "<B>RESISTOR</B>, American symbol")
      (libsource (lib "resistor") (part "R-US_R0402"))
    )
    (comp (ref "R25")
      (value "39K")
      (footprint "R0402")
      (description "<B>RESISTOR</B>, American symbol")
      (libsource (lib "resistor") (part "R-US_R0402"))
    )
    (comp (ref "R26")
      (value "20.1k")
      (footprint "R0402")
      (description "<B>RESISTOR</B>, American symbol")
      (libsource (lib "resistor") (part "R-US_R0402"))
    )
    (comp (ref "R27")
      (value "39K")
      (footprint "R0402")
      (description "<B>RESISTOR</B>, American symbol")
      (libsource (lib "resistor") (part "R-US_R0402"))
    )
    (comp (ref "R28")
      (value "20.1k")
      (footprint "R0402")
      (description "<B>RESISTOR</B>, American symbol")
      (libsource (lib "resistor") (part "R-US_R0402"))
    )
    (comp (ref "R29")
      (value "39K")
      (footprint "R0402")
      (description "<B>RESISTOR</B>, American symbol")
      (libsource (lib "resistor") (part "R-US_R0402"))
    )
    (comp (ref "R30")
      (value "20.1k")
      (footprint "R0402")
      (description "<B>RESISTOR</B>, American symbol")
      (libsource (lib "resistor") (part "R-US_R0402"))
    )
    (comp (ref "R31")
      (value "39K")
      (footprint "R0402")
      (description "<B>RESISTOR</B>, American symbol")
      (libsource (lib "resistor") (part "R-US_R0402"))
    )
    (comp (ref "R32")
      (value "20.1k")
      (footprint "R0402")
      (description "<B>RESISTOR</B>, American symbol")
      (libsource (lib "resistor") (part "R-US_R0402"))
    )
    (comp (ref "R33")
      (value "39K")
      (footprint "R0402")
      (description "<B>RESISTOR</B>, American symbol")
      (libsource (lib "resistor") (part "R-US_R0402"))
    )
    (comp (ref "R34")
      (value "20.1k")
      (footprint "R0402")
      (description "<B>RESISTOR</B>, American symbol")
      (libsource (lib "resistor") (part "R-US_R0402"))
    )
    (comp (ref "R35")
      (value "39K")
      (footprint "R0402")
      (description "<B>RESISTOR</B>, American symbol")
      (libsource (lib "resistor") (part "R-US_R0402"))
    )
    (comp (ref "R36")
      (value "20.1k")
      (footprint "R0402")
      (description "<B>RESISTOR</B>, American symbol")
      (libsource (lib "resistor") (part "R-US_R0402"))
    )
    (comp (ref "R37")
      (value "39K")
      (footprint "R0402")
      (description "<B>RESISTOR</B>, American symbol")
      (libsource (lib "resistor") (part "R-US_R0402"))
    )
    (comp (ref "R38")
      (value "20.1k")
      (footprint "R0402")
      (description "<B>RESISTOR</B>, American symbol")
      (libsource (lib "resistor") (part "R-US_R0402"))
    )
    (comp (ref "R39")
      (value "39K")
      (footprint "R0402")
      (description "<B>RESISTOR</B>, American symbol")
      (libsource (lib "resistor") (part "R-US_R0402"))
    )
    (comp (ref "R40")
      (value "1k")
      (footprint "R0402")
      (description "<B>RESISTOR</B>, American symbol")
      (libsource (lib "rcl") (part "R-US_R0402"))
    )
    (comp (ref "R41")
      (value "22")
      (footprint "R0402")
      (description "<B>RESISTOR</B>, European symbol")
      (fields (field (name "SPICEORDER 1") "SpiceOrder 1") (field (name "SPICEORDER 2") "SpiceOrder 2"))
      (libsource (lib "eagle-ltspice") (part "RR0402"))
    )
    (comp (ref "R42")
      (value "22")
      (footprint "R0402")
      (description "<B>RESISTOR</B>, European symbol")
      (fields (field (name "SPICEORDER 1") "SpiceOrder 1") (field (name "SPICEORDER 2") "SpiceOrder 2"))
      (libsource (lib "eagle-ltspice") (part "RR0402"))
    )
    (comp (ref "R43")
      (value "20.1k")
      (footprint "R0402")
      (description "<B>RESISTOR</B>, American symbol")
      (libsource (lib "resistor") (part "R-US_R0402"))
    )
    (comp (ref "R44")
      (value "39K")
      (footprint "R0402")
      (description "<B>RESISTOR</B>, American symbol")
      (libsource (lib "resistor") (part "R-US_R0402"))
    )
    (comp (ref "R45")
      (value "20.1k")
      (footprint "R0402")
      (description "<B>RESISTOR</B>, American symbol")
      (libsource (lib "resistor") (part "R-US_R0402"))
    )
    (comp (ref "R46")
      (value "39K")
      (footprint "R0402")
      (description "<B>RESISTOR</B>, American symbol")
      (libsource (lib "resistor") (part "R-US_R0402"))
    )
    (comp (ref "R47")
      (value "20.1k")
      (footprint "R0402")
      (description "<B>RESISTOR</B>, American symbol")
      (libsource (lib "resistor") (part "R-US_R0402"))
    )
    (comp (ref "R48")
      (value "39K")
      (footprint "R0402")
      (description "<B>RESISTOR</B>, American symbol")
      (libsource (lib "resistor") (part "R-US_R0402"))
    )
    (comp (ref "R49")
      (value "20.1k")
      (footprint "R0402")
      (description "<B>RESISTOR</B>, American symbol")
      (libsource (lib "resistor") (part "R-US_R0402"))
    )
    (comp (ref "R50")
      (value "39K")
      (footprint "R0402")
      (description "<B>RESISTOR</B>, American symbol")
      (libsource (lib "resistor") (part "R-US_R0402"))
    )
    (comp (ref "R51")
      (value "20.1k")
      (footprint "R0402")
      (description "<B>RESISTOR</B>, American symbol")
      (libsource (lib "resistor") (part "R-US_R0402"))
    )
    (comp (ref "R52")
      (value "39K")
      (footprint "R0402")
      (description "<B>RESISTOR</B>, American symbol")
      (libsource (lib "resistor") (part "R-US_R0402"))
    )
    (comp (ref "R53")
      (value "20.1k")
      (footprint "R0402")
      (description "<B>RESISTOR</B>, American symbol")
      (libsource (lib "resistor") (part "R-US_R0402"))
    )
    (comp (ref "R54")
      (value "39K")
      (footprint "R0402")
      (description "<B>RESISTOR</B>, American symbol")
      (libsource (lib "resistor") (part "R-US_R0402"))
    )
    (comp (ref "R55")
      (value "20.1k")
      (footprint "R0402")
      (description "<B>RESISTOR</B>, American symbol")
      (libsource (lib "resistor") (part "R-US_R0402"))
    )
    (comp (ref "R56")
      (value "39K")
      (footprint "R0402")
      (description "<B>RESISTOR</B>, American symbol")
      (libsource (lib "resistor") (part "R-US_R0402"))
    )
    (comp (ref "R57")
      (value "20.1k")
      (footprint "R0402")
      (description "<B>RESISTOR</B>, American symbol")
      (libsource (lib "resistor") (part "R-US_R0402"))
    )
    (comp (ref "R58")
      (value "39K")
      (footprint "R0402")
      (description "<B>RESISTOR</B>, American symbol")
      (libsource (lib "resistor") (part "R-US_R0402"))
    )
    (comp (ref "R59")
      (value "DNP")
      (footprint "R0402")
      (description "<B>RESISTOR</B>, American symbol")
      (libsource (lib "resistor") (part "R-US_R0402"))
    )
    (comp (ref "R61")
      (value "698")
      (footprint "R0402")
      (description "<B>RESISTOR</B>, American symbol")
      (libsource (lib "rcl") (part "R-US_R0402"))
    )
    (comp (ref "R62")
      (value "698")
      (footprint "R0402")
      (description "<B>RESISTOR</B>, American symbol")
      (libsource (lib "rcl") (part "R-US_R0402"))
    )
    (comp (ref "R63")
      (value "698")
      (footprint "R0402")
      (description "<B>RESISTOR</B>, American symbol")
      (libsource (lib "rcl") (part "R-US_R0402"))
    )
    (comp (ref "R64")
      (value "698")
      (footprint "R0402")
      (description "<B>RESISTOR</B>, American symbol")
      (libsource (lib "rcl") (part "R-US_R0402"))
    )
    (comp (ref "R65")
      (value "698")
      (footprint "R0402")
      (description "<B>RESISTOR</B>, American symbol")
      (libsource (lib "rcl") (part "R-US_R0402"))
    )
    (comp (ref "R66")
      (value "1k")
      (footprint "R0402")
      (description "<B>RESISTOR</B>, American symbol")
      (libsource (lib "rcl") (part "R-US_R0402"))
    )
    (comp (ref "R67")
      (value "1k")
      (footprint "R0402")
      (description "<B>RESISTOR</B>, American symbol")
      (libsource (lib "rcl") (part "R-US_R0402"))
    )
    (comp (ref "R68")
      (value "1k")
      (footprint "R0402")
      (description "<B>RESISTOR</B>, American symbol")
      (libsource (lib "rcl") (part "R-US_R0402"))
    )
    (comp (ref "R69")
      (value "1k")
      (footprint "R0402")
      (description "<B>RESISTOR</B>, American symbol")
      (libsource (lib "rcl") (part "R-US_R0402"))
    )
    (comp (ref "R70")
      (value "698")
      (footprint "R0402")
      (description "<B>RESISTOR</B>, American symbol")
      (libsource (lib "rcl") (part "R-US_R0402"))
    )
    (comp (ref "R71")
      (value "698")
      (footprint "R0402")
      (description "<B>RESISTOR</B>, American symbol")
      (libsource (lib "rcl") (part "R-US_R0402"))
    )
    (comp (ref "R72")
      (value "698")
      (footprint "R0402")
      (description "<B>RESISTOR</B>, American symbol")
      (libsource (lib "rcl") (part "R-US_R0402"))
    )
    (comp (ref "R73")
      (value "698")
      (footprint "R0402")
      (description "<B>RESISTOR</B>, American symbol")
      (libsource (lib "rcl") (part "R-US_R0402"))
    )
    (comp (ref "R74")
      (value "698")
      (footprint "R0402")
      (description "<B>RESISTOR</B>, American symbol")
      (libsource (lib "rcl") (part "R-US_R0402"))
    )
    (comp (ref "R75")
      (value "698")
      (footprint "R0402")
      (description "<B>RESISTOR</B>, American symbol")
      (libsource (lib "rcl") (part "R-US_R0402"))
    )
    (comp (ref "R76")
      (value "698")
      (footprint "R0402")
      (description "<B>RESISTOR</B>, American symbol")
      (libsource (lib "rcl") (part "R-US_R0402"))
    )
    (comp (ref "R77")
      (value "1k")
      (footprint "R0402")
      (description "<B>RESISTOR</B>, American symbol")
      (libsource (lib "rcl") (part "R-US_R0402"))
    )
    (comp (ref "R78")
      (value "1k")
      (footprint "R0402")
      (description "<B>RESISTOR</B>, American symbol")
      (libsource (lib "rcl") (part "R-US_R0402"))
    )
    (comp (ref "R79")
      (value "1k")
      (footprint "R0402")
      (description "<B>RESISTOR</B>, American symbol")
      (libsource (lib "rcl") (part "R-US_R0402"))
    )
    (comp (ref "R81")
      (value "698")
      (footprint "R0402")
      (description "<B>RESISTOR</B>, American symbol")
      (libsource (lib "rcl") (part "R-US_R0402"))
    )
    (comp (ref "R82")
      (value "698")
      (footprint "R0402")
      (description "<B>RESISTOR</B>, American symbol")
      (libsource (lib "rcl") (part "R-US_R0402"))
    )
    (comp (ref "R83")
      (value "698")
      (footprint "R0402")
      (description "<B>RESISTOR</B>, American symbol")
      (libsource (lib "rcl") (part "R-US_R0402"))
    )
    (comp (ref "R84")
      (value "698")
      (footprint "R0402")
      (description "<B>RESISTOR</B>, American symbol")
      (libsource (lib "rcl") (part "R-US_R0402"))
    )
    (comp (ref "R86") (value "0R") (footprint "0402") (libsource (lib "launchpad") (part "RES0402")))
    (comp (ref "R89") (value "0R") (footprint "0402") (libsource (lib "launchpad") (part "RES0402")))
    (comp (ref "R90") (value "0R") (footprint "0402") (libsource (lib "launchpad") (part "RES0402")))
    (comp (ref "R91") (value "0R") (footprint "0402") (libsource (lib "launchpad") (part "RES0402")))
    (comp (ref "R92") (value "0R") (footprint "0402") (libsource (lib "launchpad") (part "RES0402")))
    (comp (ref "R93") (value "0R") (footprint "0402") (libsource (lib "launchpad") (part "RES0402")))
    (comp (ref "R94") (value "0R") (footprint "0402") (libsource (lib "launchpad") (part "RES0402")))
    (comp (ref "R95") (value "0R") (footprint "0402") (libsource (lib "launchpad") (part "RES0402")))
    (comp (ref "R96") (value "200") (footprint "0402") (libsource (lib "launchpad") (part "RES0402")))
    (comp (ref "R97") (value "10K") (footprint "0402") (libsource (lib "launchpad") (part "RES0402")))
    (comp (ref "R98") (value "1K") (footprint "0402") (libsource (lib "launchpad") (part "RES0402")))
    (comp (ref "R99") (value "1K") (footprint "0402") (libsource (lib "launchpad") (part "RES0402")))
    (comp (ref "R100") (value "1K") (footprint "0402") (libsource (lib "launchpad") (part "RES0402")))
    (comp (ref "R101") (value "1K") (footprint "0402") (libsource (lib "launchpad") (part "RES0402")))
    (comp (ref "R102") (value "10K") (footprint "0402") (libsource (lib "launchpad") (part "RES0402")))
    (comp (ref "R103") (value "0R") (footprint "0402") (libsource (lib "launchpad") (part "RES0402")))
    (comp (ref "R104") (value "0R") (footprint "0402") (libsource (lib "launchpad") (part "RES0402")))
    (comp (ref "R105") (value "0R") (footprint "0402") (libsource (lib "launchpad") (part "RES0402")))
    (comp (ref "R106") (value "200R") (footprint "0402") (libsource (lib "launchpad") (part "RES0402")))
    (comp (ref "R107") (value "200R") (footprint "0402") (libsource (lib "launchpad") (part "RES0402")))
    (comp (ref "R108") (value "2.2K") (footprint "0402") (libsource (lib "launchpad") (part "RES0402")))
    (comp (ref "R109") (value "4.7K") (footprint "0402") (libsource (lib "launchpad") (part "RES0402")))
    (comp (ref "R110") (value "12K") (footprint "0402") (libsource (lib "launchpad") (part "RES0402")))
    (comp (ref "R111") (value "4.7K") (footprint "0402") (libsource (lib "launchpad") (part "RES0402")))
    (comp (ref "R112") (value "4.7K") (footprint "0402") (libsource (lib "launchpad") (part "RES0402")))
    (comp (ref "R113") (value "4.7K") (footprint "0402") (libsource (lib "launchpad") (part "RES0402")))
    (comp (ref "R114") (value "120R") (footprint "0402") (libsource (lib "launchpad") (part "RES0402")))
    (comp (ref "R115") (value "100K") (footprint "0402") (libsource (lib "launchpad") (part "RES0402")))
    (comp (ref "SV2")
      (value "FE15-2")
      (footprint "FE15-2")
      (description "<b>FEMALE HEADER</b>")
      (libsource (lib "con-lsta") (part "FE15-2"))
    )
    (comp (ref "TP1")
      (value "TPSB1,27")
      (footprint "B1,27")
      (description "<b>TEST PIN</b>")
      (fields (field (name "TP_SIGNAL_NAME") ">TP_SIGNAL_NAME"))
      (libsource (lib "testpad") (part "TPSB1,27"))
    )
    (comp (ref "U$5")
      (value "USB-CON-5PIN-105017-0001")
      (footprint "USB-MICRO-MOLEX-105017-0001")
      (description "<b> Molex Micro USB 105017-0001</b>")
      (libsource (lib "GeekAmmo") (part "USB-CON-5PIN-105017-0001"))
    )
    (comp (ref "U1")
      (value "LM324PW")
      (footprint "SOP65P640X120-14N")
      (description "IC QUAD OP AMP")
      (libsource (lib "Texas Instruments_By_element14_Batch_1") (part "LM324PW"))
    )
    (comp (ref "U2")
      (value "TPS70445_PWP_24")
      (footprint "PWP24_4P68X2P4")
      (description "Dual-output (3.3V/1.2V)1A/2A LDO Regulator with dual enables and SVS for split-voltage systems")
      (fields
        (field (name "GENERIC_PART_NUMBER") "TPS70445")
        (field (name "MANUFACTURER") "Texas Instruments")
      )
      (libsource (lib "TPS70445_PWP_24") (part "TPS70445_PWP_24"))
    )
    (comp (ref "U3")
      (value "LM324PW")
      (footprint "SOP65P640X120-14N")
      (description "IC QUAD OP AMP")
      (libsource (lib "Texas Instruments_By_element14_Batch_1") (part "LM324PW"))
    )
    (comp (ref "U4")
      (value "LM324PW")
      (footprint "SOP65P640X120-14N")
      (description "IC QUAD OP AMP")
      (libsource (lib "Texas Instruments_By_element14_Batch_1") (part "LM324PW"))
    )
    (comp (ref "U5")
      (value "LM324PW")
      (footprint "SOP65P640X120-14N")
      (description "IC QUAD OP AMP")
      (libsource (lib "Texas Instruments_By_element14_Batch_1") (part "LM324PW"))
    )
    (comp (ref "U6")
      (value "LM324PW")
      (footprint "SOP65P640X120-14N")
      (description "IC QUAD OP AMP")
      (libsource (lib "Texas Instruments_By_element14_Batch_1") (part "LM324PW"))
    )
    (comp (ref "U7")
      (value "RM42L432_PZ_100RM42L432_PZ_100")
      (footprint "PZ100")
      (fields (field (name "MANUFACTURER_PART_NUMBER") "rm42l432_pz_100"))
      (libsource (lib "RM42") (part "RM42L432_PZ_100RM42L432_PZ_100"))
    )
    (comp (ref "U8")
      (value "LM324PW")
      (footprint "SOP65P640X120-14N")
      (description "IC QUAD OP AMP")
      (libsource (lib "Texas Instruments_By_element14_Batch_1") (part "LM324PW"))
    )
    (comp (ref "U9")
      (value "XC2C32A-6CP56C")
      (footprint "CP56")
      (libsource (lib "launchpad") (part "XC2C32A-6CP56C"))
    )
    (comp (ref "U10") (value "FT2232HL") (footprint "LQFP64") (libsource (lib "launchpad") (part "FT2232HL")))
    (comp (ref "U11")
      (value "93LC56C-I/SN")
      (footprint "SO8")
      (libsource (lib "launchpad") (part "93LC56C-I/SN"))
    )
    (comp (ref "X1")
      (value "AS14-35")
      (footprint "AS14-35")
      (description "<b>DEUTSCH Connector</b>")
      (libsource (lib "con-deutsch") (part "AS14-35"))
    )
    (comp (ref "XTAL1")
      (value "7M-16.000MAAJ-T")
      (footprint "TXC_7M-16.000MAAJ-T")
      (description "CRYSTAL SEAM, 16MHZ, 18PF, SMD")
      (fields (field (name "1") "1") (field (name "3") "3"))
      (libsource (lib "TXC-7M-16.000MAAJ-T") (part "7M-16.000MAAJ-T"))
    )
    (comp (ref "Y1")
      (value "12M")
      (footprint "CRYSTAL_3225")
      (libsource (lib "launchpad") (part "CRYSTAL-SMD"))
    )
  )
  (nets
    (net (code "1") (name "+1V2") (class "Default")
      (node (ref "C13") (pin "1") (pinfunction "1_1") (pintype "passive"))
      (node (ref "C14") (pin "1") (pinfunction "1_1") (pintype "passive"))
      (node (ref "C15") (pin "1") (pinfunction "1_1") (pintype "passive"))
      (node (ref "C16") (pin "1") (pinfunction "1_1") (pintype "passive"))
      (node (ref "C17") (pin "1") (pinfunction "1_1") (pintype "passive"))
      (node (ref "C18") (pin "1") (pinfunction "1_1") (pintype "passive"))
      (node (ref "C19") (pin "1") (pinfunction "1_1") (pintype "passive"))
      (node (ref "C20") (pin "1") (pinfunction "1_1") (pintype "passive"))
      (node (ref "C4") (pin "1") (pinfunction "1_1") (pintype "passive"))
      (node (ref "SV2") (pin "28") (pinfunction "28_28") (pintype "passive"))
      (node (ref "U2") (pin "14") (pinfunction "VOUT2_2_14") (pintype "output"))
      (node (ref "U2") (pin "15") (pinfunction "VOUT2_15") (pintype "output"))
      (node (ref "U2") (pin "16") (pinfunction "VSENSE2/FB2_16") (pintype "passive"))
      (node (ref "U7") (pin "21") (pinfunction "VCC_2_21") (pintype "power_in"))
      (node (ref "U7") (pin "30") (pinfunction "VCC_3_30") (pintype "power_in"))
      (node (ref "U7") (pin "32") (pinfunction "VCC_4_32") (pintype "power_in"))
      (node (ref "U7") (pin "61") (pinfunction "VCC_5_61") (pintype "power_in"))
      (node (ref "U7") (pin "88") (pinfunction "VCC_6_88") (pintype "power_in"))
      (node (ref "U7") (pin "99") (pinfunction "VCC_99") (pintype "power_in"))
    )
    (net (code "2") (name "+1V8") (class "Default")
      (node (ref "C54") (pin "1") (pinfunction "1_1") (pintype "passive"))
      (node (ref "C56") (pin "1") (pinfunction "1_1") (pintype "passive"))
      (node (ref "C61") (pin "1") (pinfunction "1_1") (pintype "passive"))
      (node (ref "C62") (pin "1") (pinfunction "1_1") (pintype "passive"))
      (node (ref "C63") (pin "1") (pinfunction "1_1") (pintype "passive"))
      (node (ref "U10") (pin "12") (pinfunction "VCORE1_12") (pintype "passive"))
      (node (ref "U10") (pin "37") (pinfunction "VCORE2_37") (pintype "passive"))
      (node (ref "U10") (pin "49") (pinfunction "VREGOUT_49") (pintype "passive"))
      (node (ref "U10") (pin "64") (pinfunction "VCORE3_64") (pintype "passive"))
      (node (ref "U9") (pin "G8") (pinfunction "VCC1V8_G8") (pintype "passive"))
    )
    (net (code "3") (name "+3V3") (class "Default")
      (node (ref "C21") (pin "1") (pinfunction "1_1") (pintype "passive"))
      (node (ref "C22") (pin "1") (pinfunction "1_1") (pintype "passive"))
      (node (ref "C23") (pin "1") (pinfunction "1_1") (pintype "passive"))
      (node (ref "C24") (pin "1") (pinfunction "1_1") (pintype "passive"))
      (node (ref "C25") (pin "1") (pinfunction "1_1") (pintype "passive"))
      (node (ref "C26") (pin "1") (pinfunction "1_1") (pintype "passive"))
      (node (ref "C3") (pin "1") (pinfunction "1_1") (pintype "passive"))
      (node (ref "C46") (pin "1") (pinfunction "1_1") (pintype "passive"))
      (node (ref "C52") (pin "1") (pinfunction "1_1") (pintype "passive"))
      (node (ref "C53") (pin "1") (pinfunction "1_1") (pintype "passive"))
      (node (ref "C55") (pin "1") (pinfunction "1_1") (pintype "passive"))
      (node (ref "C57") (pin "1") (pinfunction "1_1") (pintype "passive"))
      (node (ref "C60") (pin "1") (pinfunction "1_1") (pintype "passive"))
      (node (ref "C64") (pin "1") (pinfunction "1_1") (pintype "passive"))
      (node (ref "C65") (pin "1") (pinfunction "1_1") (pintype "passive"))
      (node (ref "C66") (pin "1") (pinfunction "1_1") (pintype "passive"))
      (node (ref "C67") (pin "1") (pinfunction "1_1") (pintype "passive"))
      (node (ref "C68") (pin "1") (pinfunction "1_1") (pintype "passive"))
      (node (ref "C7") (pin "1") (pinfunction "1_1") (pintype "passive"))
      (node (ref "D27") (pin "A") (pinfunction "A_A") (pintype "passive"))
      (node (ref "D28") (pin "A") (pinfunction "A_A") (pintype "passive"))
      (node (ref "FB1") (pin "1") (pinfunction "1_1") (pintype "passive"))
      (node (ref "FB2") (pin "1") (pinfunction "1_1") (pintype "passive"))
      (node (ref "IC1") (pin "1") (pinfunction "VCC1_1") (pintype "passive"))
      (node (ref "IC2") (pin "1") (pinfunction "VCC1_1") (pintype "passive"))
      (node (ref "Q1") (pin "2") (pinfunction "S_2") (pintype "passive"))
      (node (ref "Q3") (pin "2") (pinfunction "S_2") (pintype "passive"))
      (node (ref "R1") (pin "2") (pinfunction "2_2") (pintype "passive"))
      (node (ref "R100") (pin "1") (pinfunction "1_1") (pintype "passive"))
      (node (ref "R101") (pin "1") (pinfunction "1_1") (pintype "passive"))
      (node (ref "R109") (pin "1") (pinfunction "1_1") (pintype "passive"))
      (node (ref "R111") (pin "2") (pinfunction "2_2") (pintype "passive"))
      (node (ref "R112") (pin "2") (pinfunction "2_2") (pintype "passive"))
      (node (ref "R113") (pin "2") (pinfunction "2_2") (pintype "passive"))
      (node (ref "R115") (pin "2") (pinfunction "2_2") (pintype "passive"))
      (node (ref "R2") (pin "2") (pinfunction "2_2") (pintype "passive"))
      (node (ref "R7") (pin "2") (pinfunction "2_2") (pintype "passive"))
      (node (ref "R96") (pin "1") (pinfunction "1_1") (pintype "passive"))
      (node (ref "R97") (pin "2") (pinfunction "2_2") (pintype "passive"))
      (node (ref "R98") (pin "1") (pinfunction "1_1") (pintype "passive"))
      (node (ref "R99") (pin "1") (pinfunction "1_1") (pintype "passive"))
      (node (ref "SV2") (pin "30") (pinfunction "30_30") (pintype "passive"))
      (node (ref "U1") (pin "4") (pinfunction "VCC_4") (pintype "power_in"))
      (node (ref "U10") (pin "20") (pinfunction "VCCIO1_20") (pintype "passive"))
      (node (ref "U10") (pin "31") (pinfunction "VCCIO2_31") (pintype "passive"))
      (node (ref "U10") (pin "42") (pinfunction "VCCIO3_42") (pintype "passive"))
      (node (ref "U10") (pin "50") (pinfunction "VREGIN_50") (pintype "passive"))
      (node (ref "U10") (pin "56") (pinfunction "VCCIO4_56") (pintype "passive"))
      (node (ref "U11") (pin "6") (pinfunction "ORG_6") (pintype "passive"))
      (node (ref "U11") (pin "8") (pinfunction "VCC_8") (pintype "passive"))
      (node (ref "U2") (pin "21") (pinfunction "VSENSE1/FB1_21") (pintype "passive"))
      (node (ref "U2") (pin "22") (pinfunction "VOUT1_2_22") (pintype "output"))
      (node (ref "U2") (pin "23") (pinfunction "VOUT1_23") (pintype "output"))
      (node (ref "U3") (pin "4") (pinfunction "VCC_4") (pintype "power_in"))
      (node (ref "U4") (pin "4") (pinfunction "VCC_4") (pintype "power_in"))
      (node (ref "U5") (pin "4") (pinfunction "VCC_4") (pintype "power_in"))
      (node (ref "U6") (pin "4") (pinfunction "VCC_4") (pintype "power_in"))
      (node (ref "U7") (pin "13") (pinfunction "VCCIO_3_13") (pintype "power_in"))
      (node (ref "U7") (pin "28") (pinfunction "VCCIO_4_28") (pintype "power_in"))
      (node (ref "U7") (pin "6") (pinfunction "VCCIO_2_6") (pintype "power_in"))
      (node (ref "U7") (pin "85") (pinfunction "VCCIO_85") (pintype "power_in"))
      (node (ref "U7") (pin "96") (pinfunction "VCCP_96") (pintype "power_in"))
      (node (ref "U8") (pin "4") (pinfunction "VCC_4") (pintype "power_in"))
      (node (ref "U9") (pin "C6") (pinfunction "VCCIO2_C6") (pintype "passive"))
      (node (ref "U9") (pin "D3") (pinfunction "VCCAUX_D3") (pintype "passive"))
      (node (ref "U9") (pin "H6") (pinfunction "VCCIO1_H6") (pintype "passive"))
    )
    (net (code "4") (name "+5V") (class "Default")
      (node (ref "SV2") (pin "29") (pinfunction "29_29") (pintype "passive"))
    )
    (net (code "5") (name "/5V_IN") (class "Default")
      (node (ref "F1") (pin "1") (pinfunction "1_1") (pintype "passive"))
      (node (ref "R4") (pin "1") (pinfunction "1_1") (pintype "passive"))
      (node (ref "SV2") (pin "27") (pinfunction "27_27") (pintype "passive"))
      (node (ref "U$5") (pin "1") (pinfunction "VBUS_1") (pintype "power_in"))
      (node (ref "X1") (pin "1") (pinfunction "1_1") (pintype "passive"))
    )
    (net (code "6") (name "/A0_3V3") (class "Default")
      (node (ref "R8") (pin "1") (pinfunction "1_1") (pintype "passive"))
      (node (ref "R9") (pin "2") (pinfunction "2_2") (pintype "passive"))
      (node (ref "U3") (pin "3") (pinfunction "1IN+_3") (pintype "passive"))
    )
    (net (code "7") (name "/A0_BUFFERED") (class "Default")
      (node (ref "U3") (pin "1") (pinfunction "1OUT_1") (pintype "output"))
      (node (ref "U3") (pin "2") (pinfunction "1IN-_2") (pintype "passive"))
      (node (ref "U7") (pin "42") (pinfunction "ADIN[0]_42") (pintype "passive"))
    )
    (net (code "8") (name "/A0_IN") (class "Default")
      (node (ref "D4") (pin "2") (pinfunction "2_2") (pintype "passive"))
      (node (ref "R62") (pin "2") (pinfunction "2_2") (pintype "passive"))
      (node (ref "SV2") (pin "15") (pinfunction "15_15") (pintype "passive"))
      (node (ref "X1") (pin "7") (pinfunction "1_7") (pintype "passive"))
    )
    (net (code "9") (name "/A1_3V3") (class "Default")
      (node (ref "R10") (pin "1") (pinfunction "1_1") (pintype "passive"))
      (node (ref "R11") (pin "2") (pinfunction "2_2") (pintype "passive"))
      (node (ref "U3") (pin "5") (pinfunction "2IN+_5") (pintype "passive"))
    )
    (net (code "10") (name "/A1_BUFFERED") (class "Default")
      (node (ref "U3") (pin "6") (pinfunction "2IN-_6") (pintype "passive"))
      (node (ref "U3") (pin "7") (pinfunction "2OUT_7") (pintype "output"))
      (node (ref "U7") (pin "49") (pinfunction "ADIN[1]_49") (pintype "passive"))
    )
    (net (code "11") (name "/A1_IN") (class "Default")
      (node (ref "D5") (pin "2") (pinfunction "2_2") (pintype "passive"))
      (node (ref "R73") (pin "2") (pinfunction "2_2") (pintype "passive"))
      (node (ref "SV2") (pin "13") (pinfunction "13_13") (pintype "passive"))
      (node (ref "X1") (pin "8") (pinfunction "1_8") (pintype "passive"))
    )
    (net (code "12") (name "/A2_3V3") (class "Default")
      (node (ref "R12") (pin "1") (pinfunction "1_1") (pintype "passive"))
      (node (ref "R13") (pin "2") (pinfunction "2_2") (pintype "passive"))
      (node (ref "U3") (pin "10") (pinfunction "3IN+_10") (pintype "passive"))
    )
    (net (code "13") (name "/A2_BUFFERED") (class "Default")
      (node (ref "U3") (pin "8") (pinfunction "3OUT_8") (pintype "output"))
      (node (ref "U3") (pin "9") (pinfunction "3IN-_9") (pintype "passive"))
      (node (ref "U7") (pin "51") (pinfunction "ADIN[2]_51") (pintype "passive"))
    )
    (net (code "14") (name "/A2_IN") (class "Default")
      (node (ref "D6") (pin "2") (pinfunction "2_2") (pintype "passive"))
      (node (ref "R61") (pin "2") (pinfunction "2_2") (pintype "passive"))
      (node (ref "SV2") (pin "11") (pinfunction "11_11") (pintype "passive"))
      (node (ref "X1") (pin "9") (pinfunction "1_9") (pintype "passive"))
    )
    (net (code "15") (name "/A3_3V3") (class "Default")
      (node (ref "R14") (pin "1") (pinfunction "1_1") (pintype "passive"))
      (node (ref "R15") (pin "2") (pinfunction "2_2") (pintype "passive"))
      (node (ref "U3") (pin "12") (pinfunction "4IN+_12") (pintype "passive"))
    )
    (net (code "16") (name "/A3_BUFFERED") (class "Default")
      (node (ref "U3") (pin "13") (pinfunction "4IN-_13") (pintype "passive"))
      (node (ref "U3") (pin "14") (pinfunction "4OUT_14") (pintype "output"))
      (node (ref "U7") (pin "52") (pinfunction "ADIN[3]_52") (pintype "passive"))
    )
    (net (code "17") (name "/A3_IN") (class "Default")
      (node (ref "D30") (pin "2") (pinfunction "2_2") (pintype "passive"))
      (node (ref "R84") (pin "2") (pinfunction "2_2") (pintype "passive"))
      (node (ref "SV2") (pin "9") (pinfunction "9_9") (pintype "passive"))
      (node (ref "X1") (pin "10") (pinfunction "1_10") (pintype "passive"))
    )
    (net (code "18") (name "/A4_3V3") (class "Default")
      (node (ref "R16") (pin "1") (pinfunction "1_1") (pintype "passive"))
      (node (ref "R17") (pin "2") (pinfunction "2_2") (pintype "passive"))
      (node (ref "U4") (pin "3") (pinfunction "1IN+_3") (pintype "passive"))
    )
    (net (code "19") (name "/A4_BUFFERED") (class "Default")
      (node (ref "U4") (pin "1") (pinfunction "1OUT_1") (pintype "output"))
      (node (ref "U4") (pin "2") (pinfunction "1IN-_2") (pintype "passive"))
      (node (ref "U7") (pin "54") (pinfunction "ADIN[4]_54") (pintype "passive"))
    )
    (net (code "20") (name "/A4_IN") (class "Default")
      (node (ref "D10") (pin "2") (pinfunction "2_2") (pintype "passive"))
      (node (ref "R63") (pin "2") (pinfunction "2_2") (pintype "passive"))
      (node (ref "SV2") (pin "7") (pinfunction "7_7") (pintype "passive"))
      (node (ref "X1") (pin "11") (pinfunction "1_11") (pintype "passive"))
    )
    (net (code "21") (name "/A5_3V3") (class "Default")
      (node (ref "R18") (pin "1") (pinfunction "1_1") (pintype "passive"))
      (node (ref "R19") (pin "2") (pinfunction "2_2") (pintype "passive"))
      (node (ref "U4") (pin "5") (pinfunction "2IN+_5") (pintype "passive"))
    )
    (net (code "22") (name "/A5_BUFFERED") (class "Default")
      (node (ref "U4") (pin "6") (pinfunction "2IN-_6") (pintype "passive"))
      (node (ref "U4") (pin "7") (pinfunction "2OUT_7") (pintype "output"))
      (node (ref "U7") (pin "55") (pinfunction "ADIN[5]_55") (pintype "passive"))
    )
    (net (code "23") (name "/A5_IN") (class "Default")
      (node (ref "D11") (pin "2") (pinfunction "2_2") (pintype "passive"))
      (node (ref "R72") (pin "2") (pinfunction "2_2") (pintype "passive"))
      (node (ref "SV2") (pin "5") (pinfunction "5_5") (pintype "passive"))
      (node (ref "X1") (pin "12") (pinfunction "1_12") (pintype "passive"))
    )
    (net (code "24") (name "/A6_3V3") (class "Default")
      (node (ref "R20") (pin "1") (pinfunction "1_1") (pintype "passive"))
      (node (ref "R21") (pin "2") (pinfunction "2_2") (pintype "passive"))
      (node (ref "U4") (pin "10") (pinfunction "3IN+_10") (pintype "passive"))
    )
    (net (code "25") (name "/A6_BUFFERED") (class "Default")
      (node (ref "U4") (pin "8") (pinfunction "3OUT_8") (pintype "output"))
      (node (ref "U4") (pin "9") (pinfunction "3IN-_9") (pintype "passive"))
      (node (ref "U7") (pin "56") (pinfunction "ADIN[6]_56") (pintype "passive"))
    )
    (net (code "26") (name "/A6_IN") (class "Default")
      (node (ref "D12") (pin "2") (pinfunction "2_2") (pintype "passive"))
      (node (ref "R74") (pin "2") (pinfunction "2_2") (pintype "passive"))
      (node (ref "SV2") (pin "3") (pinfunction "3_3") (pintype "passive"))
      (node (ref "X1") (pin "13") (pinfunction "1_13") (pintype "passive"))
    )
    (net (code "27") (name "/A7_3V3") (class "Default")
      (node (ref "R22") (pin "1") (pinfunction "1_1") (pintype "passive"))
      (node (ref "R23") (pin "2") (pinfunction "2_2") (pintype "passive"))
      (node (ref "U4") (pin "12") (pinfunction "4IN+_12") (pintype "passive"))
    )
    (net (code "28") (name "/A7_BUFFERED") (class "Default")
      (node (ref "U4") (pin "13") (pinfunction "4IN-_13") (pintype "passive"))
      (node (ref "U4") (pin "14") (pinfunction "4OUT_14") (pintype "output"))
      (node (ref "U7") (pin "43") (pinfunction "ADIN[7]_43") (pintype "passive"))
    )
    (net (code "29") (name "/A7_IN") (class "Default")
      (node (ref "D33") (pin "2") (pinfunction "2_2") (pintype "passive"))
      (node (ref "R83") (pin "2") (pinfunction "2_2") (pintype "passive"))
      (node (ref "SV2") (pin "1") (pinfunction "1_1") (pintype "passive"))
      (node (ref "X1") (pin "14") (pinfunction "1_14") (pintype "passive"))
    )
    (net (code "30") (name "/A8_3V3") (class "Default")
      (node (ref "R24") (pin "1") (pinfunction "1_1") (pintype "passive"))
      (node (ref "R25") (pin "2") (pinfunction "2_2") (pintype "passive"))
      (node (ref "U5") (pin "3") (pinfunction "1IN+_3") (pintype "passive"))
    )
    (net (code "31") (name "/A8_BUFFERED") (class "Default")
      (node (ref "U5") (pin "1") (pinfunction "1OUT_1") (pintype "output"))
      (node (ref "U5") (pin "2") (pinfunction "1IN-_2") (pintype "passive"))
      (node (ref "U7") (pin "57") (pinfunction "ADIN[8]_57") (pintype "passive"))
    )
    (net (code "32") (name "/A8_IN") (class "Default")
      (node (ref "D13") (pin "2") (pinfunction "2_2") (pintype "passive"))
      (node (ref "R64") (pin "2") (pinfunction "2_2") (pintype "passive"))
      (node (ref "SV2") (pin "26") (pinfunction "26_26") (pintype "passive"))
      (node (ref "X1") (pin "15") (pinfunction "1_15") (pintype "passive"))
    )
    (net (code "33") (name "/A9_3V3") (class "Default")
      (node (ref "R26") (pin "1") (pinfunction "1_1") (pintype "passive"))
      (node (ref "R27") (pin "2") (pinfunction "2_2") (pintype "passive"))
      (node (ref "U5") (pin "5") (pinfunction "2IN+_5") (pintype "passive"))
    )
    (net (code "34") (name "/A9_BUFFERED") (class "Default")
      (node (ref "U5") (pin "6") (pinfunction "2IN-_6") (pintype "passive"))
      (node (ref "U5") (pin "7") (pinfunction "2OUT_7") (pintype "output"))
      (node (ref "U7") (pin "48") (pinfunction "ADIN[9]_48") (pintype "passive"))
    )
    (net (code "35") (name "/A9_IN") (class "Default")
      (node (ref "D14") (pin "2") (pinfunction "2_2") (pintype "passive"))
      (node (ref "R71") (pin "2") (pinfunction "2_2") (pintype "passive"))
      (node (ref "SV2") (pin "24") (pinfunction "24_24") (pintype "passive"))
      (node (ref "X1") (pin "16") (pinfunction "1_16") (pintype "passive"))
    )
    (net (code "36") (name "/A10_3V3") (class "Default")
      (node (ref "R28") (pin "1") (pinfunction "1_1") (pintype "passive"))
      (node (ref "R29") (pin "2") (pinfunction "2_2") (pintype "passive"))
      (node (ref "U5") (pin "10") (pinfunction "3IN+_10") (pintype "passive"))
    )
    (net (code "37") (name "/A10_BUFFERED") (class "Default")
      (node (ref "U5") (pin "8") (pinfunction "3OUT_8") (pintype "output"))
      (node (ref "U5") (pin "9") (pinfunction "3IN-_9") (pintype "passive"))
      (node (ref "U7") (pin "50") (pinfunction "ADIN[10]_50") (pintype "passive"))
    )
    (net (code "38") (name "/A10_IN") (class "Default")
      (node (ref "D15") (pin "2") (pinfunction "2_2") (pintype "passive"))
      (node (ref "R75") (pin "2") (pinfunction "2_2") (pintype "passive"))
      (node (ref "SV2") (pin "22") (pinfunction "22_22") (pintype "passive"))
      (node (ref "X1") (pin "17") (pinfunction "1_17") (pintype "passive"))
    )
    (net (code "39") (name "/A11_3V3") (class "Default")
      (node (ref "R30") (pin "1") (pinfunction "1_1") (pintype "passive"))
      (node (ref "R31") (pin "2") (pinfunction "2_2") (pintype "passive"))
      (node (ref "U5") (pin "12") (pinfunction "4IN+_12") (pintype "passive"))
    )
    (net (code "40") (name "/A11_BUFFERED") (class "Default")
      (node (ref "U5") (pin "13") (pinfunction "4IN-_13") (pintype "passive"))
      (node (ref "U5") (pin "14") (pinfunction "4OUT_14") (pintype "output"))
      (node (ref "U7") (pin "53") (pinfunction "ADIN[11]_53") (pintype "passive"))
    )
    (net (code "41") (name "/A11_IN") (class "Default")
      (node (ref "D32") (pin "2") (pinfunction "2_2") (pintype "passive"))
      (node (ref "R82") (pin "2") (pinfunction "2_2") (pintype "passive"))
      (node (ref "SV2") (pin "20") (pinfunction "20_20") (pintype "passive"))
      (node (ref "X1") (pin "18") (pinfunction "1_18") (pintype "passive"))
    )
    (net (code "42") (name "/A12_3V3") (class "Default")
      (node (ref "R32") (pin "1") (pinfunction "1_1") (pintype "passive"))
      (node (ref "R33") (pin "2") (pinfunction "2_2") (pintype "passive"))
      (node (ref "U6") (pin "3") (pinfunction "1IN+_3") (pintype "passive"))
    )
    (net (code "43") (name "/A12_BUFFERED") (class "Default")
      (node (ref "U6") (pin "1") (pinfunction "1OUT_1") (pintype "output"))
      (node (ref "U6") (pin "2") (pinfunction "1IN-_2") (pintype "passive"))
      (node (ref "U7") (pin "40") (pinfunction "ADIN[16]_40") (pintype "passive"))
    )
    (net (code "44") (name "/A12_IN") (class "Default")
      (node (ref "D16") (pin "2") (pinfunction "2_2") (pintype "passive"))
      (node (ref "R65") (pin "2") (pinfunction "2_2") (pintype "passive"))
      (node (ref "SV2") (pin "18") (pinfunction "18_18") (pintype "passive"))
      (node (ref "X1") (pin "19") (pinfunction "1_19") (pintype "passive"))
    )
    (net (code "45") (name "/A13_3V3") (class "Default")
      (node (ref "R34") (pin "1") (pinfunction "1_1") (pintype "passive"))
      (node (ref "R35") (pin "2") (pinfunction "2_2") (pintype "passive"))
      (node (ref "U6") (pin "5") (pinfunction "2IN+_5") (pintype "passive"))
    )
    (net (code "46") (name "/A13_BUFFERED") (class "Default")
      (node (ref "U6") (pin "6") (pinfunction "2IN-_6") (pintype "passive"))
      (node (ref "U6") (pin "7") (pinfunction "2OUT_7") (pintype "output"))
      (node (ref "U7") (pin "41") (pinfunction "ADIN[17]_41") (pintype "passive"))
    )
    (net (code "47") (name "/A13_IN") (class "Default")
      (node (ref "D17") (pin "2") (pinfunction "2_2") (pintype "passive"))
      (node (ref "R70") (pin "2") (pinfunction "2_2") (pintype "passive"))
      (node (ref "X1") (pin "20") (pinfunction "1_20") (pintype "passive"))
    )
    (net (code "48") (name "/A14_3V3") (class "Default")
      (node (ref "R36") (pin "1") (pinfunction "1_1") (pintype "passive"))
      (node (ref "R37") (pin "2") (pinfunction "2_2") (pintype "passive"))
      (node (ref "U6") (pin "10") (pinfunction "3IN+_10") (pintype "passive"))
    )
    (net (code "49") (name "/A14_BUFFERED") (class "Default")
      (node (ref "U6") (pin "8") (pinfunction "3OUT_8") (pintype "output"))
      (node (ref "U6") (pin "9") (pinfunction "3IN-_9") (pintype "passive"))
      (node (ref "U7") (pin "44") (pinfunction "ADIN[20]_44") (pintype "passive"))
    )
    (net (code "50") (name "/A14_IN") (class "Default")
      (node (ref "D18") (pin "2") (pinfunction "2_2") (pintype "passive"))
      (node (ref "R76") (pin "2") (pinfunction "2_2") (pintype "passive"))
      (node (ref "X1") (pin "21") (pinfunction "1_21") (pintype "passive"))
    )
    (net (code "51") (name "/A15_3V3") (class "Default")
      (node (ref "R38") (pin "1") (pinfunction "1_1") (pintype "passive"))
      (node (ref "R39") (pin "2") (pinfunction "2_2") (pintype "passive"))
      (node (ref "U6") (pin "12") (pinfunction "4IN+_12") (pintype "passive"))
    )
    (net (code "52") (name "/A15_BUFFERED") (class "Default")
      (node (ref "U6") (pin "13") (pinfunction "4IN-_13") (pintype "passive"))
      (node (ref "U6") (pin "14") (pinfunction "4OUT_14") (pintype "output"))
      (node (ref "U7") (pin "45") (pinfunction "ADIN[21]_45") (pintype "passive"))
    )
    (net (code "53") (name "/A15_IN") (class "Default")
      (node (ref "D31") (pin "2") (pinfunction "2_2") (pintype "passive"))
      (node (ref "R81") (pin "2") (pinfunction "2_2") (pintype "passive"))
      (node (ref "X1") (pin "22") (pinfunction "1_22") (pintype "passive"))
    )
    (net (code "54") (name "/CAN1H") (class "Default")
      (node (ref "D25") (pin "1") (pinfunction "1_1") (pintype "passive"))
      (node (ref "IC1") (pin "7") (pinfunction "CANH_7") (pintype "passive"))
      (node (ref "R5") (pin "2") (pinfunction "2_2") (pintype "passive"))
      (node (ref "X1") (pin "3") (pinfunction "1_3") (pintype "passive"))
    )
    (net (code "55") (name "/CAN1L") (class "Default")
      (node (ref "D9") (pin "2") (pinfunction "2_2") (pintype "passive"))
      (node (ref "IC1") (pin "6") (pinfunction "CANL_6") (pintype "passive"))
      (node (ref "R5") (pin "1") (pinfunction "1_1") (pintype "passive"))
      (node (ref "X1") (pin "4") (pinfunction "1_4") (pintype "passive"))
    )
    (net (code "56") (name "/CAN1RX") (class "Default")
      (node (ref "IC1") (pin "2") (pinfunction "RXD_2") (pintype "passive"))
      (node (ref "SV2") (pin "23") (pinfunction "23_23") (pintype "passive"))
      (node (ref "U7") (pin "63") (pinfunction "CAN1RX_63") (pintype "passive"))
    )
    (net (code "57") (name "/CAN1TX") (class "Default")
      (node (ref "IC1") (pin "3") (pinfunction "TXD_3") (pintype "passive"))
      (node (ref "SV2") (pin "21") (pinfunction "21_21") (pintype "passive"))
      (node (ref "U7") (pin "62") (pinfunction "CAN1TX_62") (pintype "passive"))
    )
    (net (code "58") (name "/CAN2H") (class "Default")
      (node (ref "D8") (pin "1") (pinfunction "1_1") (pintype "passive"))
      (node (ref "IC2") (pin "7") (pinfunction "CANH_7") (pintype "passive"))
      (node (ref "R6") (pin "2") (pinfunction "2_2") (pintype "passive"))
      (node (ref "X1") (pin "5") (pinfunction "1_5") (pintype "passive"))
    )
    (net (code "59") (name "/CAN2L") (class "Default")
      (node (ref "D7") (pin "2") (pinfunction "2_2") (pintype "passive"))
      (node (ref "IC2") (pin "6") (pinfunction "CANL_6") (pintype "passive"))
      (node (ref "R6") (pin "1") (pinfunction "1_1") (pintype "passive"))
      (node (ref "X1") (pin "6") (pinfunction "1_6") (pintype "passive"))
    )
    (net (code "60") (name "/CAN2RX") (class "Default")
      (node (ref "IC2") (pin "2") (pinfunction "RXD_2") (pintype "passive"))
      (node (ref "SV2") (pin "19") (pinfunction "19_19") (pintype "passive"))
      (node (ref "U7") (pin "92") (pinfunction "CAN2RX_92") (pintype "passive"))
    )
    (net (code "61") (name "/CAN2TX") (class "Default")
      (node (ref "IC2") (pin "3") (pinfunction "TXD_3") (pintype "passive"))
      (node (ref "SV2") (pin "17") (pinfunction "17_17") (pintype "passive"))
      (node (ref "U7") (pin "91") (pinfunction "CAN2TX_91") (pintype "passive"))
    )
    (net (code "62") (name "/CGND") (class "Default")
      (node (ref "R59") (pin "2") (pinfunction "2_2") (pintype "passive"))
    )
    (net (code "63") (name "/CHIP_RESET") (class "Default")
      (node (ref "U2") (pin "1") (pinfunction "GND/HEATSINK_2_1") (pintype "power_in"))
      (node (ref "U2") (pin "12") (pinfunction "GND/HEATSINK_4_12") (pintype "power_in"))
      (node (ref "U2") (pin "13") (pinfunction "GND/HEATSINK_5_13") (pintype "power_in"))
      (node (ref "U2") (pin "24") (pinfunction "GND/HEATSINK_24") (pintype "power_in"))
      (node (ref "U2") (pin "6") (pinfunction "*EN1_6") (pintype "passive"))
      (node (ref "U2") (pin "7") (pinfunction "*EN2_7") (pintype "passive"))
      (node (ref "U2") (pin "9") (pinfunction "GND/HEATSINK_3_9") (pintype "power_in"))
    )
    (net (code "64") (name "/CPLD_TCK") (class "Default")
      (node (ref "U10") (pin "52") (pinfunction "BCBUS1_52") (pintype "passive"))
      (node (ref "U9") (pin "K10") (pinfunction "TCK_K10") (pintype "passive"))
    )
    (net (code "65") (name "/CPLD_TDI") (class "Default")
      (node (ref "U10") (pin "53") (pinfunction "BCBUS2_53") (pintype "passive"))
      (node (ref "U9") (pin "J10") (pinfunction "TDI_J10") (pintype "passive"))
    )
    (net (code "66") (name "/CPLD_TDO") (class "Default")
      (node (ref "U10") (pin "57") (pinfunction "BCBUS5_57") (pintype "passive"))
      (node (ref "U9") (pin "A6") (pinfunction "TDO_A6") (pintype "passive"))
    )
    (net (code "67") (name "/CPLD_TMS") (class "Default")
      (node (ref "U10") (pin "58") (pinfunction "BCBUS6_58") (pintype "passive"))
      (node (ref "U9") (pin "K9") (pinfunction "TMS_K9") (pintype "passive"))
    )
    (net (code "68") (name "/D0_3V3") (class "Default")
      (node (ref "R43") (pin "1") (pinfunction "1_1") (pintype "passive"))
      (node (ref "R44") (pin "2") (pinfunction "2_2") (pintype "passive"))
      (node (ref "U1") (pin "3") (pinfunction "1IN+_3") (pintype "passive"))
    )
    (net (code "69") (name "/D0_BUFFERED") (class "Default")
      (node (ref "U1") (pin "1") (pinfunction "1OUT_1") (pintype "output"))
      (node (ref "U1") (pin "2") (pinfunction "1IN-_2") (pintype "passive"))
      (node (ref "U7") (pin "1") (pinfunction "GIOA[0]/INT[0]_1") (pintype "passive"))
    )
    (net (code "70") (name "/D0_IN") (class "Default")
      (node (ref "D19") (pin "2") (pinfunction "2_2") (pintype "passive"))
      (node (ref "R66") (pin "2") (pinfunction "2_2") (pintype "passive"))
      (node (ref "SV2") (pin "16") (pinfunction "16_16") (pintype "passive"))
      (node (ref "X1") (pin "23") (pinfunction "1_23") (pintype "passive"))
    )
    (net (code "71") (name "/D1_3V3") (class "Default")
      (node (ref "R45") (pin "1") (pinfunction "1_1") (pintype "passive"))
      (node (ref "R46") (pin "2") (pinfunction "2_2") (pintype "passive"))
      (node (ref "U1") (pin "5") (pinfunction "2IN+_5") (pintype "passive"))
    )
    (net (code "72") (name "/D1_BUFFERED") (class "Default")
      (node (ref "U1") (pin "6") (pinfunction "2IN-_6") (pintype "passive"))
      (node (ref "U1") (pin "7") (pinfunction "2OUT_7") (pintype "output"))
      (node (ref "U7") (pin "2") (pinfunction "GIOA[1]/INT[1]_2") (pintype "passive"))
    )
    (net (code "73") (name "/D1_IN") (class "Default")
      (node (ref "D20") (pin "2") (pinfunction "2_2") (pintype "passive"))
      (node (ref "R40") (pin "2") (pinfunction "2_2") (pintype "passive"))
      (node (ref "SV2") (pin "14") (pinfunction "14_14") (pintype "passive"))
      (node (ref "X1") (pin "24") (pinfunction "1_24") (pintype "passive"))
    )
    (net (code "74") (name "/D2_3V3") (class "Default")
      (node (ref "R47") (pin "1") (pinfunction "1_1") (pintype "passive"))
      (node (ref "R48") (pin "2") (pinfunction "2_2") (pintype "passive"))
      (node (ref "U1") (pin "10") (pinfunction "3IN+_10") (pintype "passive"))
    )
    (net (code "75") (name "/D2_BUFFERED") (class "Default")
      (node (ref "U1") (pin "8") (pinfunction "3OUT_8") (pintype "output"))
      (node (ref "U1") (pin "9") (pinfunction "3IN-_9") (pintype "passive"))
      (node (ref "U7") (pin "5") (pinfunction "GIOA[2]/INT[2]_5") (pintype "passive"))
    )
    (net (code "76") (name "/D2_IN") (class "Default")
      (node (ref "D21") (pin "2") (pinfunction "2_2") (pintype "passive"))
      (node (ref "R67") (pin "2") (pinfunction "2_2") (pintype "passive"))
      (node (ref "SV2") (pin "12") (pinfunction "12_12") (pintype "passive"))
      (node (ref "X1") (pin "25") (pinfunction "1_25") (pintype "passive"))
    )
    (net (code "77") (name "/D3_3V3") (class "Default")
      (node (ref "R49") (pin "1") (pinfunction "1_1") (pintype "passive"))
      (node (ref "R50") (pin "2") (pinfunction "2_2") (pintype "passive"))
      (node (ref "U1") (pin "12") (pinfunction "4IN+_12") (pintype "passive"))
    )
    (net (code "78") (name "/D3_BUFFERED") (class "Default")
      (node (ref "U1") (pin "13") (pinfunction "4IN-_13") (pintype "passive"))
      (node (ref "U1") (pin "14") (pinfunction "4OUT_14") (pintype "output"))
      (node (ref "U7") (pin "8") (pinfunction "GIOA[3]/INT[3]_8") (pintype "passive"))
    )
    (net (code "79") (name "/D3_IN") (class "Default")
      (node (ref "D34") (pin "2") (pinfunction "2_2") (pintype "passive"))
      (node (ref "R79") (pin "2") (pinfunction "2_2") (pintype "passive"))
      (node (ref "SV2") (pin "10") (pinfunction "10_10") (pintype "passive"))
      (node (ref "X1") (pin "26") (pinfunction "1_26") (pintype "passive"))
    )
    (net (code "80") (name "/D4_3V3") (class "Default")
      (node (ref "R51") (pin "1") (pinfunction "1_1") (pintype "passive"))
      (node (ref "R52") (pin "2") (pinfunction "2_2") (pintype "passive"))
      (node (ref "U8") (pin "3") (pinfunction "1IN+_3") (pintype "passive"))
    )
    (net (code "81") (name "/D4_BUFFERED") (class "Default")
      (node (ref "U7") (pin "9") (pinfunction "GIOA[4]/INT[4]_9") (pintype "passive"))
      (node (ref "U8") (pin "1") (pinfunction "1OUT_1") (pintype "output"))
      (node (ref "U8") (pin "2") (pinfunction "1IN-_2") (pintype "passive"))
    )
    (net (code "82") (name "/D4_IN") (class "Default")
      (node (ref "D22") (pin "2") (pinfunction "2_2") (pintype "passive"))
      (node (ref "R68") (pin "2") (pinfunction "2_2") (pintype "passive"))
      (node (ref "SV2") (pin "8") (pinfunction "8_8") (pintype "passive"))
      (node (ref "X1") (pin "27") (pinfunction "1_27") (pintype "passive"))
    )
    (net (code "83") (name "/D5_3V3") (class "Default")
      (node (ref "R53") (pin "1") (pinfunction "1_1") (pintype "passive"))
      (node (ref "R54") (pin "2") (pinfunction "2_2") (pintype "passive"))
      (node (ref "U8") (pin "5") (pinfunction "2IN+_5") (pintype "passive"))
    )
    (net (code "84") (name "/D5_BUFFERED") (class "Default")
      (node (ref "U7") (pin "10") (pinfunction "GIOA[5]/INT[5]_10") (pintype "passive"))
      (node (ref "U8") (pin "6") (pinfunction "2IN-_6") (pintype "passive"))
      (node (ref "U8") (pin "7") (pinfunction "2OUT_7") (pintype "output"))
    )
    (net (code "85") (name "/D5_IN") (class "Default")
      (node (ref "D23") (pin "2") (pinfunction "2_2") (pintype "passive"))
      (node (ref "R69") (pin "2") (pinfunction "2_2") (pintype "passive"))
      (node (ref "SV2") (pin "6") (pinfunction "6_6") (pintype "passive"))
      (node (ref "X1") (pin "28") (pinfunction "1_28") (pintype "passive"))
    )
    (net (code "86") (name "/D6_3V3") (class "Default")
      (node (ref "R55") (pin "1") (pinfunction "1_1") (pintype "passive"))
      (node (ref "R56") (pin "2") (pinfunction "2_2") (pintype "passive"))
      (node (ref "U8") (pin "10") (pinfunction "3IN+_10") (pintype "passive"))
    )
    (net (code "87") (name "/D6_BUFFERED") (class "Default")
      (node (ref "U7") (pin "12") (pinfunction "GIOA[6]/INT[6]_12") (pintype "passive"))
      (node (ref "U8") (pin "8") (pinfunction "3OUT_8") (pintype "output"))
      (node (ref "U8") (pin "9") (pinfunction "3IN-_9") (pintype "passive"))
    )
    (net (code "88") (name "/D6_IN") (class "Default")
      (node (ref "D24") (pin "2") (pinfunction "2_2") (pintype "passive"))
      (node (ref "R77") (pin "2") (pinfunction "2_2") (pintype "passive"))
      (node (ref "SV2") (pin "4") (pinfunction "4_4") (pintype "passive"))
      (node (ref "X1") (pin "29") (pinfunction "1_29") (pintype "passive"))
    )
    (net (code "89") (name "/D7_3V3") (class "Default")
      (node (ref "R57") (pin "1") (pinfunction "1_1") (pintype "passive"))
      (node (ref "R58") (pin "2") (pinfunction "2_2") (pintype "passive"))
      (node (ref "U8") (pin "12") (pinfunction "4IN+_12") (pintype "passive"))
    )
    (net (code "90") (name "/D7_BUFFERED") (class "Default")
      (node (ref "U7") (pin "18") (pinfunction "GIOA[7]/INT[7]_18") (pintype "passive"))
      (node (ref "U8") (pin "13") (pinfunction "4IN-_13") (pintype "passive"))
      (node (ref "U8") (pin "14") (pinfunction "4OUT_14") (pintype "output"))
    )
    (net (code "91") (name "/D7_IN") (class "Default")
      (node (ref "D35") (pin "2") (pinfunction "2_2") (pintype "passive"))
      (node (ref "R78") (pin "2") (pinfunction "2_2") (pintype "passive"))
      (node (ref "SV2") (pin "2") (pinfunction "2_2") (pintype "passive"))
      (node (ref "X1") (pin "30") (pinfunction "1_30") (pintype "passive"))
    )
    (net (code "92") (name "/DM") (class "Default")
      (node (ref "R41") (pin "2") (pinfunction "2_2") (pintype "passive"))
      (node (ref "U10") (pin "7") (pinfunction "DM_7") (pintype "passive"))
    )
    (net (code "93") (name "/DP") (class "Default")
      (node (ref "R42") (pin "2") (pinfunction "2_2") (pintype "passive"))
      (node (ref "U10") (pin "8") (pinfunction "DP_8") (pintype "passive"))
    )
    (net (code "94") (name "/FTDI_TCK") (class "Default")
      (node (ref "U10") (pin "16") (pinfunction "ADBUS0_16") (pintype "passive"))
      (node (ref "U9") (pin "H10") (pinfunction "IO12_14_H10") (pintype "passive"))
    )
    (net (code "95") (name "/FTDI_TDI") (class "Default")
      (node (ref "Q1") (pin "3") (pinfunction "G_3") (pintype "passive"))
      (node (ref "R115") (pin "1") (pinfunction "1_1") (pintype "passive"))
      (node (ref "U10") (pin "17") (pinfunction "ADBUS1_17") (pintype "passive"))
      (node (ref "U9") (pin "K8") (pinfunction "IO12_13_K8") (pintype "passive"))
    )
    (net (code "96") (name "/FTDI_TDO") (class "Default")
      (node (ref "U10") (pin "18") (pinfunction "ADBUS2_18") (pintype "passive"))
      (node (ref "U9") (pin "H8") (pinfunction "IO12_12_H8") (pintype "passive"))
    )
    (net (code "97") (name "/FTDI_TMS") (class "Default")
      (node (ref "U10") (pin "19") (pinfunction "ADBUS3_19") (pintype "passive"))
      (node (ref "U9") (pin "H5") (pinfunction "IO12_11_H5") (pintype "passive"))
    )
    (net (code "98") (name "/GPIOH0") (class "Default")
      (node (ref "U10") (pin "26") (pinfunction "ACBUS0_26") (pintype "passive"))
      (node (ref "U9") (pin "K1") (pinfunction "IO12_6_K1") (pintype "passive"))
    )
    (net (code "99") (name "/GPIOH1") (class "Default")
      (node (ref "U10") (pin "27") (pinfunction "ACBUS1_27") (pintype "passive"))
      (node (ref "U9") (pin "J1") (pinfunction "IO12_5_J1") (pintype "passive"))
    )
    (net (code "100") (name "/GPIOH3") (class "Default")
      (node (ref "U10") (pin "29") (pinfunction "ACBUS3_29") (pintype "passive"))
      (node (ref "U9") (pin "F3") (pinfunction "IO12_2_F3") (pintype "passive"))
    )
    (net (code "101") (name "/GPIOL0") (class "Default")
      (node (ref "U10") (pin "21") (pinfunction "ADBUS4_21") (pintype "passive"))
      (node (ref "U9") (pin "K5") (pinfunction "IO12_10_K5") (pintype "passive"))
    )
    (net (code "102") (name "/GPIOL1") (class "Default")
      (node (ref "U10") (pin "22") (pinfunction "ADBUS5_22") (pintype "passive"))
      (node (ref "U9") (pin "H3") (pinfunction "IO12_9_H3") (pintype "passive"))
    )
    (net (code "103") (name "/GPIOL2") (class "Default")
      (node (ref "U10") (pin "23") (pinfunction "ADBUS6_23") (pintype "passive"))
      (node (ref "U9") (pin "K3") (pinfunction "IO12_8_K3") (pintype "passive"))
    )
    (net (code "104") (name "/GPIOL3") (class "Default")
      (node (ref "U10") (pin "24") (pinfunction "ADBUS7_24") (pintype "passive"))
      (node (ref "U9") (pin "K2") (pinfunction "IO12_7_K2") (pintype "passive"))
    )
    (net (code "105") (name "/JTAG_SEL") (class "Default")
      (node (ref "Q3") (pin "3") (pinfunction "G_3") (pintype "passive"))
    )
    (net (code "106") (name "/MCU_RESET") (class "Default")
      (node (ref "R89") (pin "1") (pinfunction "1_1") (pintype "passive"))
    )
    (net (code "107") (name "/MCU_RTCK") (class "Default")
      (node (ref "R86") (pin "2") (pinfunction "2_2") (pintype "passive"))
    )
    (net (code "108") (name "/MCU_TCK") (class "Default")
      (node (ref "R90") (pin "1") (pinfunction "1_1") (pintype "passive"))
    )
    (net (code "109") (name "/MCU_TDI") (class "Default")
      (node (ref "R93") (pin "1") (pinfunction "1_1") (pintype "passive"))
    )
    (net (code "110") (name "/MCU_TDO") (class "Default")
      (node (ref "R91") (pin "1") (pinfunction "1_1") (pintype "passive"))
    )
    (net (code "111") (name "/MCU_TMS") (class "Default")
      (node (ref "R95") (pin "1") (pinfunction "1_1") (pintype "passive"))
    )
    (net (code "112") (name "/MCU_TRSTN") (class "Default")
      (node (ref "R94") (pin "1") (pinfunction "1_1") (pintype "passive"))
    )
    (net (code "113") (name "/POWERGOOD") (class "Default")
      (node (ref "C51") (pin "1") (pinfunction "1_1") (pintype "passive"))
      (node (ref "R97") (pin "1") (pinfunction "1_1") (pintype "passive"))
      (node (ref "U9") (pin "F10") (pinfunction "IO12_16_F10") (pintype "passive"))
    )
    (net (code "114") (name "/POWER_EN") (class "Default")
      (node (ref "D26") (pin "C") (pinfunction "C_C") (pintype "passive"))
      (node (ref "U10") (pin "60") (pinfunction "PWREN_60") (pintype "passive"))
      (node (ref "U9") (pin "G3") (pinfunction "IO12_4_G3") (pintype "passive"))
    )
    (net (code "115") (name "/PWR_DET") (class "Default")
      (node (ref "U10") (pin "28") (pinfunction "ACBUS2_28") (pintype "passive"))
      (node (ref "U9") (pin "H1") (pinfunction "IO12_3_H1") (pintype "passive"))
    )
    (net (code "116") (name "/SCI1_RX") (class "Default")
      (node (ref "R103") (pin "2") (pinfunction "2_2") (pintype "passive"))
    )
    (net (code "117") (name "/SCI1_TX") (class "Default")
      (node (ref "R104") (pin "2") (pinfunction "2_2") (pintype "passive"))
    )
    (net (code "118") (name "/SPARE0") (class "Default")
      (node (ref "R98") (pin "2") (pinfunction "2_2") (pintype "passive"))
      (node (ref "U10") (pin "30") (pinfunction "ACBUS4_30") (pintype "passive"))
      (node (ref "U9") (pin "F1") (pinfunction "IO21_1_F1") (pintype "passive"))
    )
    (net (code "119") (name "/SPARE1") (class "Default")
      (node (ref "R99") (pin "2") (pinfunction "2_2") (pintype "passive"))
      (node (ref "U10") (pin "32") (pinfunction "ACBUS5_32") (pintype "passive"))
      (node (ref "U9") (pin "E3") (pinfunction "IO21_2_E3") (pintype "passive"))
    )
    (net (code "120") (name "/SPARE2") (class "Default")
      (node (ref "R100") (pin "2") (pinfunction "2_2") (pintype "passive"))
      (node (ref "U10") (pin "33") (pinfunction "ACBUS6_33") (pintype "passive"))
      (node (ref "U9") (pin "E1") (pinfunction "IO21_3_E1") (pintype "passive"))
    )
    (net (code "121") (name "/SPARE3") (class "Default")
      (node (ref "R101") (pin "2") (pinfunction "2_2") (pintype "passive"))
      (node (ref "U10") (pin "34") (pinfunction "ACBUS7_34") (pintype "passive"))
      (node (ref "U9") (pin "D1") (pinfunction "IO21_4_D1") (pintype "passive"))
    )
    (net (code "122") (name "/SUSPEED") (class "Default")
      (node (ref "U10") (pin "36") (pinfunction "SUSPEED_36") (pintype "passive"))
      (node (ref "U9") (pin "G1") (pinfunction "IO12_1_G1") (pintype "passive"))
    )
    (net (code "123") (name "/T_DIS") (class "Default")
      (node (ref "Q3") (pin "1") (pinfunction "D_1") (pintype "passive"))
      (node (ref "R102") (pin "2") (pinfunction "2_2") (pintype "passive"))
      (node (ref "R92") (pin "1") (pinfunction "1_1") (pintype "passive"))
    )
    (net (code "124") (name "3.3V") (class "Default")
      (node (ref "C1") (pin "1") (pinfunction "1_1") (pintype "passive"))
      (node (ref "C10") (pin "1") (pinfunction "1_1") (pintype "passive"))
      (node (ref "C2") (pin "1") (pinfunction "1_1") (pintype "passive"))
      (node (ref "C5") (pin "-") (pinfunction "+_-") (pintype "passive"))
      (node (ref "C6") (pin "1") (pinfunction "1_1") (pintype "passive"))
      (node (ref "C9") (pin "1") (pinfunction "1_1") (pintype "passive"))
      (node (ref "F1") (pin "2") (pinfunction "2_2") (pintype "passive"))
      (node (ref "IC1") (pin "8") (pinfunction "VCC2_8") (pintype "passive"))
      (node (ref "IC2") (pin "8") (pinfunction "VCC2_8") (pintype "passive"))
      (node (ref "R3") (pin "2") (pinfunction "2_2") (pintype "passive"))
      (node (ref "U2") (pin "10") (pinfunction "VIN2_2_10") (pintype "passive"))
      (node (ref "U2") (pin "11") (pinfunction "VIN2_11") (pintype "passive"))
      (node (ref "U2") (pin "2") (pinfunction "VIN1_2_2") (pintype "passive"))
      (node (ref "U2") (pin "3") (pinfunction "VIN1_3") (pintype "passive"))
    )
    (net (code "125") (name "GND") (class "Default")
      (node (ref "C1") (pin "2") (pinfunction "2_2") (pintype "passive"))
      (node (ref "C10") (pin "2") (pinfunction "2_2") (pintype "passive"))
      (node (ref "C11") (pin "2") (pinfunction "2_2") (pintype "passive"))
      (node (ref "C12") (pin "2") (pinfunction "2_2") (pintype "passive"))
      (node (ref "C13") (pin "2") (pinfunction "2_2") (pintype "passive"))
      (node (ref "C14") (pin "2") (pinfunction "2_2") (pintype "passive"))
      (node (ref "C15") (pin "2") (pinfunction "2_2") (pintype "passive"))
      (node (ref "C16") (pin "2") (pinfunction "2_2") (pintype "passive"))
      (node (ref "C17") (pin "2") (pinfunction "2_2") (pintype "passive"))
      (node (ref "C18") (pin "2") (pinfunction "2_2") (pintype "passive"))
      (node (ref "C19") (pin "2") (pinfunction "2_2") (pintype "passive"))
      (node (ref "C2") (pin "2") (pinfunction "2_2") (pintype "passive"))
      (node (ref "C20") (pin "2") (pinfunction "2_2") (pintype "passive"))
      (node (ref "C21") (pin "2") (pinfunction "2_2") (pintype "passive"))
      (node (ref "C22") (pin "2") (pinfunction "2_2") (pintype "passive"))
      (node (ref "C23") (pin "2") (pinfunction "2_2") (pintype "passive"))
      (node (ref "C24") (pin "2") (pinfunction "2_2") (pintype "passive"))
      (node (ref "C25") (pin "2") (pinfunction "2_2") (pintype "passive"))
      (node (ref "C26") (pin "2") (pinfunction "2_2") (pintype "passive"))
      (node (ref "C29") (pin "2") (pinfunction "2_2") (pintype "passive"))
      (node (ref "C3") (pin "2") (pinfunction "2_2") (pintype "passive"))
      (node (ref "C30") (pin "2") (pinfunction "2_2") (pintype "passive"))
      (node (ref "C31") (pin "2") (pinfunction "2_2") (pintype "passive"))
      (node (ref "C32") (pin "2") (pinfunction "2_2") (pintype "passive"))
      (node (ref "C33") (pin "2") (pinfunction "2_2") (pintype "passive"))
      (node (ref "C34") (pin "2") (pinfunction "2_2") (pintype "passive"))
      (node (ref "C35") (pin "2") (pinfunction "2_2") (pintype "passive"))
      (node (ref "C36") (pin "2") (pinfunction "2_2") (pintype "passive"))
      (node (ref "C37") (pin "2") (pinfunction "2_2") (pintype "passive"))
      (node (ref "C38") (pin "2") (pinfunction "2_2") (pintype "passive"))
      (node (ref "C39") (pin "2") (pinfunction "2_2") (pintype "passive"))
      (node (ref "C4") (pin "2") (pinfunction "2_2") (pintype "passive"))
      (node (ref "C40") (pin "2") (pinfunction "2_2") (pintype "passive"))
      (node (ref "C41") (pin "2") (pinfunction "2_2") (pintype "passive"))
      (node (ref "C42") (pin "2") (pinfunction "2_2") (pintype "passive"))
      (node (ref "C43") (pin "2") (pinfunction "2_2") (pintype "passive"))
      (node (ref "C44") (pin "2") (pinfunction "2_2") (pintype "passive"))
      (node (ref "C45") (pin "2") (pinfunction "2_2") (pintype "passive"))
      (node (ref "C46") (pin "2") (pinfunction "2_2") (pintype "passive"))
      (node (ref "C47") (pin "2") (pinfunction "2_2") (pintype "passive"))
      (node (ref "C48") (pin "2") (pinfunction "2_2") (pintype "passive"))
      (node (ref "C49") (pin "2") (pinfunction "2_2") (pintype "passive"))
      (node (ref "C5") (pin "+") (pinfunction "-_+") (pintype "passive"))
      (node (ref "C50") (pin "2") (pinfunction "2_2") (pintype "passive"))
      (node (ref "C51") (pin "2") (pinfunction "2_2") (pintype "passive"))
      (node (ref "C52") (pin "2") (pinfunction "2_2") (pintype "passive"))
      (node (ref "C53") (pin "2") (pinfunction "2_2") (pintype "passive"))
      (node (ref "C54") (pin "2") (pinfunction "2_2") (pintype "passive"))
      (node (ref "C55") (pin "2") (pinfunction "2_2") (pintype "passive"))
      (node (ref "C56") (pin "2") (pinfunction "2_2") (pintype "passive"))
      (node (ref "C57") (pin "2") (pinfunction "2_2") (pintype "passive"))
      (node (ref "C58") (pin "2") (pinfunction "2_2") (pintype "passive"))
      (node (ref "C59") (pin "2") (pinfunction "2_2") (pintype "passive"))
      (node (ref "C6") (pin "2") (pinfunction "2_2") (pintype "passive"))
      (node (ref "C60") (pin "2") (pinfunction "2_2") (pintype "passive"))
      (node (ref "C61") (pin "2") (pinfunction "2_2") (pintype "passive"))
      (node (ref "C62") (pin "2") (pinfunction "2_2") (pintype "passive"))
      (node (ref "C63") (pin "2") (pinfunction "2_2") (pintype "passive"))
      (node (ref "C64") (pin "2") (pinfunction "2_2") (pintype "passive"))
      (node (ref "C65") (pin "2") (pinfunction "2_2") (pintype "passive"))
      (node (ref "C66") (pin "2") (pinfunction "2_2") (pintype "passive"))
      (node (ref "C67") (pin "2") (pinfunction "2_2") (pintype "passive"))
      (node (ref "C68") (pin "2") (pinfunction "2_2") (pintype "passive"))
      (node (ref "C69") (pin "2") (pinfunction "2_2") (pintype "passive"))
      (node (ref "C7") (pin "2") (pinfunction "2_2") (pintype "passive"))
      (node (ref "C70") (pin "2") (pinfunction "2_2") (pintype "passive"))
      (node (ref "C71") (pin "2") (pinfunction "2_2") (pintype "passive"))
      (node (ref "C72") (pin "2") (pinfunction "2_2") (pintype "passive"))
      (node (ref "C8") (pin "2") (pinfunction "2_2") (pintype "passive"))
      (node (ref "C9") (pin "2") (pinfunction "2_2") (pintype "passive"))
      (node (ref "D10") (pin "1") (pinfunction "1_1") (pintype "passive"))
      (node (ref "D11") (pin "1") (pinfunction "1_1") (pintype "passive"))
      (node (ref "D12") (pin "1") (pinfunction "1_1") (pintype "passive"))
      (node (ref "D13") (pin "1") (pinfunction "1_1") (pintype "passive"))
      (node (ref "D14") (pin "1") (pinfunction "1_1") (pintype "passive"))
      (node (ref "D15") (pin "1") (pinfunction "1_1") (pintype "passive"))
      (node (ref "D16") (pin "1") (pinfunction "1_1") (pintype "passive"))
      (node (ref "D17") (pin "1") (pinfunction "1_1") (pintype "passive"))
      (node (ref "D18") (pin "1") (pinfunction "1_1") (pintype "passive"))
      (node (ref "D19") (pin "1") (pinfunction "1_1") (pintype "passive"))
      (node (ref "D2") (pin "1") (pinfunction "1_1") (pintype "passive"))
      (node (ref "D20") (pin "1") (pinfunction "1_1") (pintype "passive"))
      (node (ref "D21") (pin "1") (pinfunction "1_1") (pintype "passive"))
      (node (ref "D22") (pin "1") (pinfunction "1_1") (pintype "passive"))
      (node (ref "D23") (pin "1") (pinfunction "1_1") (pintype "passive"))
      (node (ref "D24") (pin "1") (pinfunction "1_1") (pintype "passive"))
      (node (ref "D25") (pin "2") (pinfunction "2_2") (pintype "passive"))
      (node (ref "D29") (pin "C") (pinfunction "C_C") (pintype "passive"))
      (node (ref "D3") (pin "1") (pinfunction "1_1") (pintype "passive"))
      (node (ref "D30") (pin "1") (pinfunction "1_1") (pintype "passive"))
      (node (ref "D31") (pin "1") (pinfunction "1_1") (pintype "passive"))
      (node (ref "D32") (pin "1") (pinfunction "1_1") (pintype "passive"))
      (node (ref "D33") (pin "1") (pinfunction "1_1") (pintype "passive"))
      (node (ref "D34") (pin "1") (pinfunction "1_1") (pintype "passive"))
      (node (ref "D35") (pin "1") (pinfunction "1_1") (pintype "passive"))
      (node (ref "D4") (pin "1") (pinfunction "1_1") (pintype "passive"))
      (node (ref "D5") (pin "1") (pinfunction "1_1") (pintype "passive"))
      (node (ref "D6") (pin "1") (pinfunction "1_1") (pintype "passive"))
      (node (ref "D7") (pin "1") (pinfunction "1_1") (pintype "passive"))
      (node (ref "D8") (pin "2") (pinfunction "2_2") (pintype "passive"))
      (node (ref "D9") (pin "1") (pinfunction "1_1") (pintype "passive"))
      (node (ref "IC1") (pin "4") (pinfunction "GND1_4") (pintype "passive"))
      (node (ref "IC1") (pin "5") (pinfunction "GND2_5") (pintype "passive"))
      (node (ref "IC2") (pin "4") (pinfunction "GND1_4") (pintype "passive"))
      (node (ref "IC2") (pin "5") (pinfunction "GND2_5") (pintype "passive"))
      (node (ref "LED1") (pin "C@1") (pinfunction "C_C@1") (pintype "passive"))
      (node (ref "R102") (pin "1") (pinfunction "1_1") (pintype "passive"))
      (node (ref "R11") (pin "1") (pinfunction "1_1") (pintype "passive"))
      (node (ref "R110") (pin "1") (pinfunction "1_1") (pintype "passive"))
      (node (ref "R13") (pin "1") (pinfunction "1_1") (pintype "passive"))
      (node (ref "R15") (pin "1") (pinfunction "1_1") (pintype "passive"))
      (node (ref "R17") (pin "1") (pinfunction "1_1") (pintype "passive"))
      (node (ref "R19") (pin "1") (pinfunction "1_1") (pintype "passive"))
      (node (ref "R21") (pin "1") (pinfunction "1_1") (pintype "passive"))
      (node (ref "R23") (pin "1") (pinfunction "1_1") (pintype "passive"))
      (node (ref "R25") (pin "1") (pinfunction "1_1") (pintype "passive"))
      (node (ref "R27") (pin "1") (pinfunction "1_1") (pintype "passive"))
      (node (ref "R29") (pin "1") (pinfunction "1_1") (pintype "passive"))
      (node (ref "R31") (pin "1") (pinfunction "1_1") (pintype "passive"))
      (node (ref "R33") (pin "1") (pinfunction "1_1") (pintype "passive"))
      (node (ref "R35") (pin "1") (pinfunction "1_1") (pintype "passive"))
      (node (ref "R37") (pin "1") (pinfunction "1_1") (pintype "passive"))
      (node (ref "R39") (pin "1") (pinfunction "1_1") (pintype "passive"))
      (node (ref "R4") (pin "2") (pinfunction "2_2") (pintype "passive"))
      (node (ref "R44") (pin "1") (pinfunction "1_1") (pintype "passive"))
      (node (ref "R46") (pin "1") (pinfunction "1_1") (pintype "passive"))
      (node (ref "R48") (pin "1") (pinfunction "1_1") (pintype "passive"))
      (node (ref "R50") (pin "1") (pinfunction "1_1") (pintype "passive"))
      (node (ref "R52") (pin "1") (pinfunction "1_1") (pintype "passive"))
      (node (ref "R54") (pin "1") (pinfunction "1_1") (pintype "passive"))
      (node (ref "R56") (pin "1") (pinfunction "1_1") (pintype "passive"))
      (node (ref "R58") (pin "1") (pinfunction "1_1") (pintype "passive"))
      (node (ref "R59") (pin "1") (pinfunction "1_1") (pintype "passive"))
      (node (ref "R9") (pin "1") (pinfunction "1_1") (pintype "passive"))
      (node (ref "SV2") (pin "25") (pinfunction "25_25") (pintype "passive"))
      (node (ref "U$5") (pin "5") (pinfunction "GND_5") (pintype "power_in"))
      (node (ref "U1") (pin "11") (pinfunction "GND_11") (pintype "passive"))
      (node (ref "U10") (pin "1") (pinfunction "GND1_1") (pintype "passive"))
      (node (ref "U10") (pin "10") (pinfunction "GNDA_10") (pintype "passive"))
      (node (ref "U10") (pin "11") (pinfunction "GND3_11") (pintype "passive"))
      (node (ref "U10") (pin "13") (pinfunction "TEST_13") (pintype "passive"))
      (node (ref "U10") (pin "15") (pinfunction "GND4_15") (pintype "passive"))
      (node (ref "U10") (pin "25") (pinfunction "GND5_25") (pintype "passive"))
      (node (ref "U10") (pin "35") (pinfunction "GND6_35") (pintype "passive"))
      (node (ref "U10") (pin "47") (pinfunction "GND7_47") (pintype "passive"))
      (node (ref "U10") (pin "5") (pinfunction "GND2_5") (pintype "passive"))
      (node (ref "U10") (pin "51") (pinfunction "GND8_51") (pintype "passive"))
      (node (ref "U11") (pin "5") (pinfunction "GND_5") (pintype "passive"))
      (node (ref "U3") (pin "11") (pinfunction "GND_11") (pintype "passive"))
      (node (ref "U4") (pin "11") (pinfunction "GND_11") (pintype "passive"))
      (node (ref "U5") (pin "11") (pinfunction "GND_11") (pintype "passive"))
      (node (ref "U6") (pin "11") (pinfunction "GND_11") (pintype "passive"))
      (node (ref "U7") (pin "100") (pinfunction "VSS_100") (pintype "power_in"))
      (node (ref "U7") (pin "17") (pinfunction "VSS_3_17") (pintype "power_in"))
      (node (ref "U7") (pin "20") (pinfunction "VSS_4_20") (pintype "power_in"))
      (node (ref "U7") (pin "29") (pinfunction "VSS_5_29") (pintype "power_in"))
      (node (ref "U7") (pin "33") (pinfunction "VSS_6_33") (pintype "power_in"))
      (node (ref "U7") (pin "59") (pinfunction "VSS_7_59") (pintype "power_in"))
      (node (ref "U7") (pin "7") (pinfunction "VSS_2_7") (pintype "power_in"))
      (node (ref "U7") (pin "72") (pinfunction "VSS_8_72") (pintype "power_in"))
      (node (ref "U7") (pin "86") (pinfunction "VSS_9_86") (pintype "power_in"))
      (node (ref "U7") (pin "87") (pinfunction "VSS_10_87") (pintype "power_in"))
      (node (ref "U8") (pin "11") (pinfunction "GND_11") (pintype "passive"))
      (node (ref "U9") (pin "C7") (pinfunction "GND3_C7") (pintype "passive"))
      (node (ref "U9") (pin "F8") (pinfunction "GND2_F8") (pintype "passive"))
      (node (ref "U9") (pin "H4") (pinfunction "GND1_H4") (pintype "passive"))
      (node (ref "X1") (pin "2") (pinfunction "1_2") (pintype "passive"))
      (node (ref "Y1") (pin "P$2") (pinfunction "P$2_P$2") (pintype "passive"))
      (node (ref "Y1") (pin "P$4") (pinfunction "P$4_P$4") (pintype "passive"))
    )
    (net (code "126") (name "Net-(C8-Pad1)") (class "Default")
      (node (ref "C8") (pin "1") (pinfunction "1_1") (pintype "passive"))
      (node (ref "R51") (pin "2") (pinfunction "2_2") (pintype "passive"))
      (node (ref "R68") (pin "1") (pinfunction "1_1") (pintype "passive"))
    )
    (net (code "127") (name "Net-(C11-Pad1)") (class "Default")
      (node (ref "C11") (pin "1") (pinfunction "1_1") (pintype "passive"))
      (node (ref "R12") (pin "2") (pinfunction "2_2") (pintype "passive"))
      (node (ref "R61") (pin "1") (pinfunction "1_1") (pintype "passive"))
    )
    (net (code "128") (name "Net-(C12-Pad1)") (class "Default")
      (node (ref "C12") (pin "1") (pinfunction "1_1") (pintype "passive"))
      (node (ref "R62") (pin "1") (pinfunction "1_1") (pintype "passive"))
      (node (ref "R8") (pin "2") (pinfunction "2_2") (pintype "passive"))
    )
    (net (code "129") (name "Net-(C29-Pad1)") (class "Default")
      (node (ref "C29") (pin "1") (pinfunction "1_1") (pintype "passive"))
      (node (ref "R16") (pin "2") (pinfunction "2_2") (pintype "passive"))
      (node (ref "R63") (pin "1") (pinfunction "1_1") (pintype "passive"))
    )
    (net (code "130") (name "Net-(C30-Pad1)") (class "Default")
      (node (ref "C30") (pin "1") (pinfunction "1_1") (pintype "passive"))
      (node (ref "R24") (pin "2") (pinfunction "2_2") (pintype "passive"))
      (node (ref "R64") (pin "1") (pinfunction "1_1") (pintype "passive"))
    )
    (net (code "131") (name "Net-(C31-Pad1)") (class "Default")
      (node (ref "C31") (pin "1") (pinfunction "1_1") (pintype "passive"))
      (node (ref "R32") (pin "2") (pinfunction "2_2") (pintype "passive"))
      (node (ref "R65") (pin "1") (pinfunction "1_1") (pintype "passive"))
    )
    (net (code "132") (name "Net-(C32-Pad1)") (class "Default")
      (node (ref "C32") (pin "1") (pinfunction "1_1") (pintype "passive"))
      (node (ref "R43") (pin "2") (pinfunction "2_2") (pintype "passive"))
      (node (ref "R66") (pin "1") (pinfunction "1_1") (pintype "passive"))
    )
    (net (code "133") (name "Net-(C33-Pad1)") (class "Default")
      (node (ref "C33") (pin "1") (pinfunction "1_1") (pintype "passive"))
      (node (ref "R53") (pin "2") (pinfunction "2_2") (pintype "passive"))
      (node (ref "R69") (pin "1") (pinfunction "1_1") (pintype "passive"))
    )
    (net (code "134") (name "Net-(C34-Pad1)") (class "Default")
      (node (ref "C34") (pin "1") (pinfunction "1_1") (pintype "passive"))
      (node (ref "R47") (pin "2") (pinfunction "2_2") (pintype "passive"))
      (node (ref "R67") (pin "1") (pinfunction "1_1") (pintype "passive"))
    )
    (net (code "135") (name "Net-(C35-Pad1)") (class "Default")
      (node (ref "C35") (pin "1") (pinfunction "1_1") (pintype "passive"))
      (node (ref "R40") (pin "1") (pinfunction "1_1") (pintype "passive"))
      (node (ref "R45") (pin "2") (pinfunction "2_2") (pintype "passive"))
    )
    (net (code "136") (name "Net-(C36-Pad1)") (class "Default")
      (node (ref "C36") (pin "1") (pinfunction "1_1") (pintype "passive"))
      (node (ref "R34") (pin "2") (pinfunction "2_2") (pintype "passive"))
      (node (ref "R70") (pin "1") (pinfunction "1_1") (pintype "passive"))
    )
    (net (code "137") (name "Net-(C37-Pad1)") (class "Default")
      (node (ref "C37") (pin "1") (pinfunction "1_1") (pintype "passive"))
      (node (ref "R26") (pin "2") (pinfunction "2_2") (pintype "passive"))
      (node (ref "R71") (pin "1") (pinfunction "1_1") (pintype "passive"))
    )
    (net (code "138") (name "Net-(C38-Pad1)") (class "Default")
      (node (ref "C38") (pin "1") (pinfunction "1_1") (pintype "passive"))
      (node (ref "R18") (pin "2") (pinfunction "2_2") (pintype "passive"))
      (node (ref "R72") (pin "1") (pinfunction "1_1") (pintype "passive"))
    )
    (net (code "139") (name "Net-(C39-Pad1)") (class "Default")
      (node (ref "C39") (pin "1") (pinfunction "1_1") (pintype "passive"))
      (node (ref "R10") (pin "2") (pinfunction "2_2") (pintype "passive"))
      (node (ref "R73") (pin "1") (pinfunction "1_1") (pintype "passive"))
    )
    (net (code "140") (name "Net-(C40-Pad1)") (class "Default")
      (node (ref "C40") (pin "1") (pinfunction "1_1") (pintype "passive"))
      (node (ref "R20") (pin "2") (pinfunction "2_2") (pintype "passive"))
      (node (ref "R74") (pin "1") (pinfunction "1_1") (pintype "passive"))
    )
    (net (code "141") (name "Net-(C41-Pad1)") (class "Default")
      (node (ref "C41") (pin "1") (pinfunction "1_1") (pintype "passive"))
      (node (ref "R28") (pin "2") (pinfunction "2_2") (pintype "passive"))
      (node (ref "R75") (pin "1") (pinfunction "1_1") (pintype "passive"))
    )
    (net (code "142") (name "Net-(C42-Pad1)") (class "Default")
      (node (ref "C42") (pin "1") (pinfunction "1_1") (pintype "passive"))
      (node (ref "R36") (pin "2") (pinfunction "2_2") (pintype "passive"))
      (node (ref "R76") (pin "1") (pinfunction "1_1") (pintype "passive"))
    )
    (net (code "143") (name "Net-(C43-Pad1)") (class "Default")
      (node (ref "C43") (pin "1") (pinfunction "1_1") (pintype "passive"))
      (node (ref "R55") (pin "2") (pinfunction "2_2") (pintype "passive"))
      (node (ref "R77") (pin "1") (pinfunction "1_1") (pintype "passive"))
    )
    (net (code "144") (name "Net-(C44-Pad1)") (class "Default")
      (node (ref "C44") (pin "1") (pinfunction "1_1") (pintype "passive"))
      (node (ref "R57") (pin "2") (pinfunction "2_2") (pintype "passive"))
      (node (ref "R78") (pin "1") (pinfunction "1_1") (pintype "passive"))
    )
    (net (code "145") (name "Net-(C45-Pad1)") (class "Default")
      (node (ref "C45") (pin "1") (pinfunction "1_1") (pintype "passive"))
      (node (ref "R49") (pin "2") (pinfunction "2_2") (pintype "passive"))
      (node (ref "R79") (pin "1") (pinfunction "1_1") (pintype "passive"))
    )
    (net (code "146") (name "Net-(C47-Pad1)") (class "Default")
      (node (ref "C47") (pin "1") (pinfunction "1_1") (pintype "passive"))
      (node (ref "R38") (pin "2") (pinfunction "2_2") (pintype "passive"))
      (node (ref "R81") (pin "1") (pinfunction "1_1") (pintype "passive"))
    )
    (net (code "147") (name "Net-(C48-Pad1)") (class "Default")
      (node (ref "C48") (pin "1") (pinfunction "1_1") (pintype "passive"))
      (node (ref "R30") (pin "2") (pinfunction "2_2") (pintype "passive"))
      (node (ref "R82") (pin "1") (pinfunction "1_1") (pintype "passive"))
    )
    (net (code "148") (name "Net-(C49-Pad1)") (class "Default")
      (node (ref "C49") (pin "1") (pinfunction "1_1") (pintype "passive"))
      (node (ref "R22") (pin "2") (pinfunction "2_2") (pintype "passive"))
      (node (ref "R83") (pin "1") (pinfunction "1_1") (pintype "passive"))
    )
    (net (code "149") (name "Net-(C50-Pad1)") (class "Default")
      (node (ref "C50") (pin "1") (pinfunction "1_1") (pintype "passive"))
      (node (ref "R14") (pin "2") (pinfunction "2_2") (pintype "passive"))
      (node (ref "R84") (pin "1") (pinfunction "1_1") (pintype "passive"))
    )
    (net (code "150") (name "Net-(D26-PadA)") (class "Default")
      (node (ref "D26") (pin "A") (pinfunction "A_A") (pintype "passive"))
      (node (ref "R96") (pin "2") (pinfunction "2_2") (pintype "passive"))
    )
    (net (code "151") (name "Net-(D27-PadC)") (class "Default")
      (node (ref "D27") (pin "C") (pinfunction "C_C") (pintype "passive"))
      (node (ref "R106") (pin "2") (pinfunction "2_2") (pintype "passive"))
    )
    (net (code "152") (name "Net-(D28-PadC)") (class "Default")
      (node (ref "D28") (pin "C") (pinfunction "C_C") (pintype "passive"))
      (node (ref "R107") (pin "2") (pinfunction "2_2") (pintype "passive"))
    )
    (net (code "153") (name "Net-(D29-PadA)") (class "Default")
      (node (ref "D29") (pin "A") (pinfunction "A_A") (pintype "passive"))
      (node (ref "R114") (pin "1") (pinfunction "1_1") (pintype "passive"))
    )
    (net (code "154") (name "Net-(LED1-A)") (class "Default")
      (node (ref "LED1") (pin "A@1") (pinfunction "A_A@1") (pintype "passive"))
      (node (ref "R3") (pin "1") (pinfunction "1_1") (pintype "passive"))
    )
    (net (code "155") (name "Net-(Q1-D)") (class "Default")
      (node (ref "Q1") (pin "1") (pinfunction "D_1") (pintype "passive"))
      (node (ref "R114") (pin "2") (pinfunction "2_2") (pintype "passive"))
    )
    (net (code "156") (name "Net-(U$5-D+)") (class "Default")
      (node (ref "D3") (pin "2") (pinfunction "2_2") (pintype "passive"))
      (node (ref "R42") (pin "1") (pinfunction "1_1") (pintype "passive"))
      (node (ref "U$5") (pin "3") (pinfunction "D+_3") (pintype "passive"))
    )
    (net (code "157") (name "Net-(U$5-D-)") (class "Default")
      (node (ref "D2") (pin "2") (pinfunction "2_2") (pintype "passive"))
      (node (ref "R41") (pin "1") (pinfunction "1_1") (pintype "passive"))
      (node (ref "U$5") (pin "2") (pinfunction "D-_2") (pintype "passive"))
    )
    (net (code "158") (name "Net-(U2-*MR)") (class "Default")
      (node (ref "R1") (pin "1") (pinfunction "1_1") (pintype "passive"))
      (node (ref "R2") (pin "1") (pinfunction "1_1") (pintype "passive"))
      (node (ref "U2") (pin "18") (pinfunction "PG2_18") (pintype "output"))
      (node (ref "U2") (pin "19") (pinfunction "PG1_19") (pintype "output"))
      (node (ref "U2") (pin "5") (pinfunction "*MR_5") (pintype "passive"))
    )
    (net (code "159") (name "Net-(U2-*RESET)") (class "Default")
      (node (ref "R7") (pin "1") (pinfunction "1_1") (pintype "passive"))
      (node (ref "U2") (pin "8") (pinfunction "*RESET_8") (pintype "output"))
    )
    (net (code "160") (name "Net-(U7-KELVIN_GND)") (class "Default")
      (node (ref "C27") (pin "2") (pinfunction "2_2") (pintype "passive"))
      (node (ref "C28") (pin "1") (pinfunction "1_1") (pintype "passive"))
      (node (ref "U7") (pin "15") (pinfunction "KELVIN_GND_15") (pintype "passive"))
    )
    (net (code "161") (name "Net-(U7-OSCIN)") (class "Default")
      (node (ref "C27") (pin "1") (pinfunction "1_1") (pintype "passive"))
      (node (ref "U7") (pin "14") (pinfunction "OSCIN_14") (pintype "passive"))
      (node (ref "XTAL1") (pin "1") (pinfunction "1_1") (pintype "passive"))
    )
    (net (code "162") (name "Net-(U7-OSCOUT)") (class "Default")
      (node (ref "C28") (pin "2") (pinfunction "2_2") (pintype "passive"))
      (node (ref "U7") (pin "16") (pinfunction "OSCOUT_16") (pintype "passive"))
      (node (ref "XTAL1") (pin "3") (pinfunction "3_3") (pintype "passive"))
    )
    (net (code "163") (name "Net-(U9-I)") (class "Default")
      (node (ref "R86") (pin "1") (pinfunction "1_1") (pintype "passive"))
      (node (ref "U9") (pin "D10") (pinfunction "I_D10") (pintype "passive"))
    )
    (net (code "164") (name "Net-(U9-IO21_5)") (class "Default")
      (node (ref "R95") (pin "2") (pinfunction "2_2") (pintype "passive"))
      (node (ref "U9") (pin "A3") (pinfunction "IO21_6_A3") (pintype "passive"))
      (node (ref "U9") (pin "C1") (pinfunction "IO21_5_C1") (pintype "passive"))
    )
    (net (code "165") (name "Net-(U9-IO21_7)") (class "Default")
      (node (ref "R94") (pin "2") (pinfunction "2_2") (pintype "passive"))
      (node (ref "U9") (pin "A2") (pinfunction "IO21_7_A2") (pintype "passive"))
    )
    (net (code "166") (name "Net-(U9-IO21_8)") (class "Default")
      (node (ref "R93") (pin "2") (pinfunction "2_2") (pintype "passive"))
      (node (ref "U9") (pin "B1") (pinfunction "IO21_8_B1") (pintype "passive"))
    )
    (net (code "167") (name "Net-(U9-IO21_9)") (class "Default")
      (node (ref "R92") (pin "2") (pinfunction "2_2") (pintype "passive"))
      (node (ref "U9") (pin "A1") (pinfunction "IO21_9_A1") (pintype "passive"))
    )
    (net (code "168") (name "Net-(U9-IO21_10)") (class "Default")
      (node (ref "R91") (pin "2") (pinfunction "2_2") (pintype "passive"))
      (node (ref "U9") (pin "C4") (pinfunction "IO21_10_C4") (pintype "passive"))
    )
    (net (code "169") (name "Net-(U9-IO21_11)") (class "Default")
      (node (ref "R90") (pin "2") (pinfunction "2_2") (pintype "passive"))
      (node (ref "U9") (pin "A10") (pinfunction "IO21_13_A10") (pintype "passive"))
      (node (ref "U9") (pin "C5") (pinfunction "IO21_11_C5") (pintype "passive"))
      (node (ref "U9") (pin "C8") (pinfunction "IO21_12_C8") (pintype "passive"))
    )
    (net (code "170") (name "Net-(U9-IO21_14)") (class "Default")
      (node (ref "R89") (pin "2") (pinfunction "2_2") (pintype "passive"))
      (node (ref "U9") (pin "B10") (pinfunction "IO21_14_B10") (pintype "passive"))
    )
    (net (code "171") (name "Net-(U10-BCBUS3)") (class "Default")
      (node (ref "R106") (pin "1") (pinfunction "1_1") (pintype "passive"))
      (node (ref "U10") (pin "54") (pinfunction "BCBUS3_54") (pintype "passive"))
    )
    (net (code "172") (name "Net-(U10-BCBUS4)") (class "Default")
      (node (ref "R107") (pin "1") (pinfunction "1_1") (pintype "passive"))
      (node (ref "U10") (pin "55") (pinfunction "BCBUS4_55") (pintype "passive"))
    )
    (net (code "173") (name "Net-(U10-BDBUS0)") (class "Default")
      (node (ref "R103") (pin "1") (pinfunction "1_1") (pintype "passive"))
      (node (ref "U10") (pin "38") (pinfunction "BDBUS0_38") (pintype "passive"))
    )
    (net (code "174") (name "Net-(U10-BDBUS1)") (class "Default")
      (node (ref "R104") (pin "1") (pinfunction "1_1") (pintype "passive"))
      (node (ref "U10") (pin "39") (pinfunction "BDBUS1_39") (pintype "passive"))
    )
    (net (code "175") (name "Net-(U10-BDBUS2)") (class "Default")
      (node (ref "R105") (pin "2") (pinfunction "2_2") (pintype "passive"))
      (node (ref "U10") (pin "40") (pinfunction "BDBUS2_40") (pintype "passive"))
    )
    (net (code "176") (name "Net-(U10-BDBUS3)") (class "Default")
      (node (ref "R105") (pin "1") (pinfunction "1_1") (pintype "passive"))
      (node (ref "U10") (pin "41") (pinfunction "BDBUS3_41") (pintype "passive"))
    )
    (net (code "177") (name "Net-(U10-EECLK)") (class "Default")
      (node (ref "R112") (pin "1") (pinfunction "1_1") (pintype "passive"))
      (node (ref "U10") (pin "62") (pinfunction "EECLK_62") (pintype "passive"))
      (node (ref "U11") (pin "2") (pinfunction "SK_2") (pintype "passive"))
    )
    (net (code "178") (name "Net-(U10-EECS)") (class "Default")
      (node (ref "R111") (pin "1") (pinfunction "1_1") (pintype "passive"))
      (node (ref "U10") (pin "63") (pinfunction "EECS_63") (pintype "passive"))
      (node (ref "U11") (pin "1") (pinfunction "CS_1") (pintype "passive"))
    )
    (net (code "179") (name "Net-(U10-EEDATA)") (class "Default")
      (node (ref "R108") (pin "2") (pinfunction "2_2") (pintype "passive"))
      (node (ref "U10") (pin "61") (pinfunction "EEDATA_61") (pintype "passive"))
      (node (ref "U11") (pin "3") (pinfunction "DIN_3") (pintype "passive"))
    )
    (net (code "180") (name "Net-(U10-OSCI)") (class "Default")
      (node (ref "C72") (pin "1") (pinfunction "1_1") (pintype "passive"))
      (node (ref "U10") (pin "2") (pinfunction "OSCI_2") (pintype "passive"))
      (node (ref "Y1") (pin "P$3") (pinfunction "P$3_P$3") (pintype "passive"))
    )
    (net (code "181") (name "Net-(U10-OSCO)") (class "Default")
      (node (ref "C71") (pin "1") (pinfunction "1_1") (pintype "passive"))
      (node (ref "U10") (pin "3") (pinfunction "OSCO_3") (pintype "passive"))
      (node (ref "Y1") (pin "P$1") (pinfunction "P$1_P$1") (pintype "passive"))
    )
    (net (code "182") (name "Net-(U10-REF)") (class "Default")
      (node (ref "R110") (pin "2") (pinfunction "2_2") (pintype "passive"))
      (node (ref "U10") (pin "6") (pinfunction "REF_6") (pintype "passive"))
    )
    (net (code "183") (name "Net-(U10-RESET)") (class "Default")
      (node (ref "R109") (pin "2") (pinfunction "2_2") (pintype "passive"))
      (node (ref "U10") (pin "14") (pinfunction "RESET_14") (pintype "passive"))
    )
    (net (code "184") (name "Net-(U10-VPHY)") (class "Default")
      (node (ref "C59") (pin "1") (pinfunction "1_1") (pintype "passive"))
      (node (ref "C70") (pin "1") (pinfunction "1_1") (pintype "passive"))
      (node (ref "FB2") (pin "2") (pinfunction "2_2") (pintype "passive"))
      (node (ref "U10") (pin "4") (pinfunction "VPHY_4") (pintype "passive"))
    )
    (net (code "185") (name "Net-(U10-VPLL)") (class "Default")
      (node (ref "C58") (pin "1") (pinfunction "1_1") (pintype "passive"))
      (node (ref "C69") (pin "1") (pinfunction "1_1") (pintype "passive"))
      (node (ref "FB1") (pin "2") (pinfunction "2_2") (pintype "passive"))
      (node (ref "U10") (pin "9") (pinfunction "VPLL_9") (pintype "passive"))
    )
    (net (code "186") (name "Net-(U11-DOUT)") (class "Default")
      (node (ref "R108") (pin "1") (pinfunction "1_1") (pintype "passive"))
      (node (ref "R113") (pin "1") (pinfunction "1_1") (pintype "passive"))
      (node (ref "U11") (pin "4") (pinfunction "DOUT_4") (pintype "passive"))
    )
    (net (code "187") (name "unconnected-(TP1-PP-PadTP)") (class "Default")
      (node (ref "TP1") (pin "TP") (pinfunction "PP_TP") (pintype "passive"))
    )
    (net (code "188") (name "unconnected-(U$5-ID-Pad4)") (class "Default")
      (node (ref "U$5") (pin "4") (pinfunction "ID_4") (pintype "passive"))
    )
    (net (code "189") (name "unconnected-(U2-NC-Pad20)") (class "Default")
      (node (ref "U2") (pin "20") (pinfunction "NC_20") (pintype "passive"))
    )
    (net (code "190") (name "unconnected-(U2-NC_2-Pad4)") (class "Default")
      (node (ref "U2") (pin "4") (pinfunction "NC_2_4") (pintype "passive"))
    )
    (net (code "191") (name "unconnected-(U2-NC_3-Pad17)") (class "Default")
      (node (ref "U2") (pin "17") (pinfunction "NC_3_17") (pintype "passive"))
    )
    (net (code "192") (name "unconnected-(U2-PadEPAD)") (class "Default")
      (node (ref "U2") (pin "EPAD") (pinfunction "EPAD_EPAD") (pintype "passive"))
    )
    (net (code "193") (name "unconnected-(U7-ADEVT-Pad58)") (class "Default")
      (node (ref "U7") (pin "58") (pinfunction "ADEVT_58") (pintype "passive"))
    )
    (net (code "194") (name "unconnected-(U7-ECLK-Pad84)") (class "Default")
      (node (ref "U7") (pin "84") (pinfunction "ECLK_84") (pintype "passive"))
    )
    (net (code "195") (name "unconnected-(U7-FLTP1-Pad3)") (class "Default")
      (node (ref "U7") (pin "3") (pinfunction "FLTP1_3") (pintype "passive"))
    )
    (net (code "196") (name "unconnected-(U7-FLTP2-Pad4)") (class "Default")
      (node (ref "U7") (pin "4") (pinfunction "FLTP2_4") (pintype "passive"))
    )
    (net (code "197") (name "unconnected-(U7-LINRX-Pad94)") (class "Default")
      (node (ref "U7") (pin "94") (pinfunction "LINRX_94") (pintype "passive"))
    )
    (net (code "198") (name "unconnected-(U7-LINTX-Pad95)") (class "Default")
      (node (ref "U7") (pin "95") (pinfunction "LINTX_95") (pintype "passive"))
    )
    (net (code "199") (name "unconnected-(U7-MIBSPI1CLK-Pad67)") (class "Default")
      (node (ref "U7") (pin "67") (pinfunction "MIBSPI1CLK_67") (pintype "passive"))
    )
    (net (code "200") (name "unconnected-(U7-MIBSPI1NCS[0]-Pad73)") (class "Default")
      (node (ref "U7") (pin "73") (pinfunction "MIBSPI1NCS[0]_73") (pintype "passive"))
    )
    (net (code "201") (name "unconnected-(U7-MIBSPI1NCS[1]-Pad93)") (class "Default")
      (node (ref "U7") (pin "93") (pinfunction "MIBSPI1NCS[1]_93") (pintype "passive"))
    )
    (net (code "202") (name "unconnected-(U7-MIBSPI1NCS[2]-Pad27)") (class "Default")
      (node (ref "U7") (pin "27") (pinfunction "MIBSPI1NCS[2]_27") (pintype "passive"))
    )
    (net (code "203") (name "unconnected-(U7-MIBSPI1NCS[3]-Pad39)") (class "Default")
      (node (ref "U7") (pin "39") (pinfunction "MIBSPI1NCS[3]_39") (pintype "passive"))
    )
    (net (code "204") (name "unconnected-(U7-MIBSPI1NENA-Pad68)") (class "Default")
      (node (ref "U7") (pin "68") (pinfunction "MIBSPI1NENA_68") (pintype "passive"))
    )
    (net (code "205") (name "unconnected-(U7-MIBSPI1SIMO-Pad65)") (class "Default")
      (node (ref "U7") (pin "65") (pinfunction "MIBSPI1SIMO_65") (pintype "passive"))
    )
    (net (code "206") (name "unconnected-(U7-MIBSPI1SOMI-Pad66)") (class "Default")
      (node (ref "U7") (pin "66") (pinfunction "MIBSPI1SOMI_66") (pintype "passive"))
    )
    (net (code "207") (name "unconnected-(U7-N2HET[0]-Pad19)") (class "Default")
      (node (ref "U7") (pin "19") (pinfunction "N2HET[0]_19") (pintype "passive"))
    )
    (net (code "208") (name "unconnected-(U7-N2HET[2]-Pad22)") (class "Default")
      (node (ref "U7") (pin "22") (pinfunction "N2HET[2]_22") (pintype "passive"))
    )
    (net (code "209") (name "unconnected-(U7-N2HET[4]-Pad25)") (class "Default")
      (node (ref "U7") (pin "25") (pinfunction "N2HET[4]_25") (pintype "passive"))
    )
    (net (code "210") (name "unconnected-(U7-N2HET[6]-Pad26)") (class "Default")
      (node (ref "U7") (pin "26") (pinfunction "N2HET[6]_26") (pintype "passive"))
    )
    (net (code "211") (name "unconnected-(U7-N2HET[8]-Pad74)") (class "Default")
      (node (ref "U7") (pin "74") (pinfunction "N2HET[8]_74") (pintype "passive"))
    )
    (net (code "212") (name "unconnected-(U7-N2HET[10-Pad83)") (class "Default")
      (node (ref "U7") (pin "83") (pinfunction "N2HET[10_83") (pintype "passive"))
    )
    (net (code "213") (name "unconnected-(U7-N2HET[12]-Pad89)") (class "Default")
      (node (ref "U7") (pin "89") (pinfunction "N2HET[12]_89") (pintype "passive"))
    )
    (net (code "214") (name "unconnected-(U7-N2HET[14]-Pad90)") (class "Default")
      (node (ref "U7") (pin "90") (pinfunction "N2HET[14]_90") (pintype "passive"))
    )
    (net (code "215") (name "unconnected-(U7-N2HET[16]-Pad97)") (class "Default")
      (node (ref "U7") (pin "97") (pinfunction "N2HET[16]_97") (pintype "passive"))
    )
    (net (code "216") (name "unconnected-(U7-N2HET[18]-Pad98)") (class "Default")
      (node (ref "U7") (pin "98") (pinfunction "N2HET[18]_98") (pintype "passive"))
    )
    (net (code "217") (name "unconnected-(U7-N2HET[022]-Pad11)") (class "Default")
      (node (ref "U7") (pin "11") (pinfunction "N2HET[022]_11") (pintype "passive"))
    )
    (net (code "218") (name "unconnected-(U7-N2HET[024]-Pad64)") (class "Default")
      (node (ref "U7") (pin "64") (pinfunction "N2HET[024]_64") (pintype "passive"))
    )
    (net (code "219") (name "unconnected-(U7-NERROR-Pad82)") (class "Default")
      (node (ref "U7") (pin "82") (pinfunction "NERROR_82") (pintype "passive"))
    )
    (net (code "220") (name "unconnected-(U7-NPORRST-Pad31)") (class "Default")
      (node (ref "U7") (pin "31") (pinfunction "NPORRST_31") (pintype "passive"))
    )
    (net (code "221") (name "unconnected-(U7-NRST-Pad81)") (class "Default")
      (node (ref "U7") (pin "81") (pinfunction "NRST_81") (pintype "passive"))
    )
    (net (code "222") (name "unconnected-(U7-NTRST-Pad76)") (class "Default")
      (node (ref "U7") (pin "76") (pinfunction "NTRST_76") (pintype "passive"))
    )
    (net (code "223") (name "unconnected-(U7-RTCK-Pad80)") (class "Default")
      (node (ref "U7") (pin "80") (pinfunction "RTCK_80") (pintype "passive"))
    )
    (net (code "224") (name "unconnected-(U7-SPI2CLK-Pad71)") (class "Default")
      (node (ref "U7") (pin "71") (pinfunction "SPI2CLK_71") (pintype "passive"))
    )
    (net (code "225") (name "unconnected-(U7-SPI2NCS[0]-Pad23)") (class "Default")
      (node (ref "U7") (pin "23") (pinfunction "SPI2NCS[0]_23") (pintype "passive"))
    )
    (net (code "226") (name "unconnected-(U7-SPI2SIMO-Pad70)") (class "Default")
      (node (ref "U7") (pin "70") (pinfunction "SPI2SIMO_70") (pintype "passive"))
    )
    (net (code "227") (name "unconnected-(U7-SPI2SOMI-Pad69)") (class "Default")
      (node (ref "U7") (pin "69") (pinfunction "SPI2SOMI_69") (pintype "passive"))
    )
    (net (code "228") (name "unconnected-(U7-SPI3CLK-Pad36)") (class "Default")
      (node (ref "U7") (pin "36") (pinfunction "SPI3CLK_36") (pintype "passive"))
    )
    (net (code "229") (name "unconnected-(U7-SPI3NCS[0]-Pad38)") (class "Default")
      (node (ref "U7") (pin "38") (pinfunction "SPI3NCS[0]_38") (pintype "passive"))
    )
    (net (code "230") (name "unconnected-(U7-SPI3NENA-Pad37)") (class "Default")
      (node (ref "U7") (pin "37") (pinfunction "SPI3NENA_37") (pintype "passive"))
    )
    (net (code "231") (name "unconnected-(U7-SPI3SIMO-Pad35)") (class "Default")
      (node (ref "U7") (pin "35") (pinfunction "SPI3SIMO_35") (pintype "passive"))
    )
    (net (code "232") (name "unconnected-(U7-SPI3SOMI-Pad34)") (class "Default")
      (node (ref "U7") (pin "34") (pinfunction "SPI3SOMI_34") (pintype "passive"))
    )
    (net (code "233") (name "unconnected-(U7-TCK-Pad79)") (class "Default")
      (node (ref "U7") (pin "79") (pinfunction "TCK_79") (pintype "passive"))
    )
    (net (code "234") (name "unconnected-(U7-TDI-Pad77)") (class "Default")
      (node (ref "U7") (pin "77") (pinfunction "TDI_77") (pintype "passive"))
    )
    (net (code "235") (name "unconnected-(U7-TDO-Pad78)") (class "Default")
      (node (ref "U7") (pin "78") (pinfunction "TDO_78") (pintype "passive"))
    )
    (net (code "236") (name "unconnected-(U7-TEST-Pad24)") (class "Default")
      (node (ref "U7") (pin "24") (pinfunction "TEST_24") (pintype "passive"))
    )
    (net (code "237") (name "unconnected-(U7-TMS-Pad75)") (class "Default")
      (node (ref "U7") (pin "75") (pinfunction "TMS_75") (pintype "passive"))
    )
    (net (code "238") (name "unconnected-(U7-VCCAD{slash}ADREFHI-Pad46)") (class "Default")
      (node (ref "U7") (pin "46") (pinfunction "VCCAD/ADREFHI_46") (pintype "passive"))
    )
    (net (code "239") (name "unconnected-(U7-VCCIO_5-Pad60)") (class "Default")
      (node (ref "U7") (pin "60") (pinfunction "VCCIO_5_60") (pintype "power_in"))
    )
    (net (code "240") (name "unconnected-(U7-VSSAD{slash}ADREFLO-Pad47)") (class "Default")
      (node (ref "U7") (pin "47") (pinfunction "VSSAD/ADREFLO_47") (pintype "passive"))
    )
    (net (code "241") (name "unconnected-(U9-IO12_15-PadG10)") (class "Default")
      (node (ref "U9") (pin "G10") (pinfunction "IO12_15_G10") (pintype "passive"))
    )
    (net (code "242") (name "unconnected-(U9-IO21_15-PadC10)") (class "Default")
      (node (ref "U9") (pin "C10") (pinfunction "IO21_15_C10") (pintype "passive"))
    )
    (net (code "243") (name "unconnected-(U9-IO21_16-PadE8)") (class "Default")
      (node (ref "U9") (pin "E8") (pinfunction "IO21_16_E8") (pintype "passive"))
    )
    (net (code "244") (name "unconnected-(U9-NC1-PadD8)") (class "Default")
      (node (ref "U9") (pin "D8") (pinfunction "NC1_D8") (pintype "passive"))
    )
    (net (code "245") (name "unconnected-(U9-NC2-PadE10)") (class "Default")
      (node (ref "U9") (pin "E10") (pinfunction "NC2_E10") (pintype "passive"))
    )
    (net (code "246") (name "unconnected-(U9-NC3-PadH7)") (class "Default")
      (node (ref "U9") (pin "H7") (pinfunction "NC3_H7") (pintype "passive"))
    )
    (net (code "247") (name "unconnected-(U9-NC4-PadK4)") (class "Default")
      (node (ref "U9") (pin "K4") (pinfunction "NC4_K4") (pintype "passive"))
    )
    (net (code "248") (name "unconnected-(U9-NC5-PadK6)") (class "Default")
      (node (ref "U9") (pin "K6") (pinfunction "NC5_K6") (pintype "passive"))
    )
    (net (code "249") (name "unconnected-(U9-NC6-PadA4)") (class "Default")
      (node (ref "U9") (pin "A4") (pinfunction "NC6_A4") (pintype "passive"))
    )
    (net (code "250") (name "unconnected-(U9-NC7-PadA5)") (class "Default")
      (node (ref "U9") (pin "A5") (pinfunction "NC7_A5") (pintype "passive"))
    )
    (net (code "251") (name "unconnected-(U9-NC8-PadA7)") (class "Default")
      (node (ref "U9") (pin "A7") (pinfunction "NC8_A7") (pintype "passive"))
    )
    (net (code "252") (name "unconnected-(U9-NC9-PadA8)") (class "Default")
      (node (ref "U9") (pin "A8") (pinfunction "NC9_A8") (pintype "passive"))
    )
    (net (code "253") (name "unconnected-(U9-NC10-PadA9)") (class "Default")
      (node (ref "U9") (pin "A9") (pinfunction "NC10_A9") (pintype "passive"))
    )
    (net (code "254") (name "unconnected-(U9-NC11-PadC3)") (class "Default")
      (node (ref "U9") (pin "C3") (pinfunction "NC11_C3") (pintype "passive"))
    )
    (net (code "255") (name "unconnected-(U9-NC12-PadK7)") (class "Default")
      (node (ref "U9") (pin "K7") (pinfunction "NC12_K7") (pintype "passive"))
    )
    (net (code "256") (name "unconnected-(U10-BCBUS0-Pad48)") (class "Default")
      (node (ref "U10") (pin "48") (pinfunction "BCBUS0_48") (pintype "passive"))
    )
    (net (code "257") (name "unconnected-(U10-BCBUS7-Pad59)") (class "Default")
      (node (ref "U10") (pin "59") (pinfunction "BCBUS7_59") (pintype "passive"))
    )
    (net (code "258") (name "unconnected-(U10-BDBUS4-Pad43)") (class "Default")
      (node (ref "U10") (pin "43") (pinfunction "BDBUS4_43") (pintype "passive"))
    )
    (net (code "259") (name "unconnected-(U10-BDBUS5-Pad44)") (class "Default")
      (node (ref "U10") (pin "44") (pinfunction "BDBUS5_44") (pintype "passive"))
    )
    (net (code "260") (name "unconnected-(U10-BDBUS6-Pad45)") (class "Default")
      (node (ref "U10") (pin "45") (pinfunction "BDBUS6_45") (pintype "passive"))
    )
    (net (code "261") (name "unconnected-(U10-BDBUS7-Pad46)") (class "Default")
      (node (ref "U10") (pin "46") (pinfunction "BDBUS7_46") (pintype "passive"))
    )
    (net (code "262") (name "unconnected-(U11-NC-Pad7)") (class "Default")
      (node (ref "U11") (pin "7") (pinfunction "NC_7") (pintype "passive"))
    )
    (net (code "263") (name "unconnected-(X1AE-1-Pad31)") (class "Default")
      (node (ref "X1") (pin "31") (pinfunction "1_31") (pintype "passive"))
    )
    (net (code "264") (name "unconnected-(X1AF-1-Pad32)") (class "Default")
      (node (ref "X1") (pin "32") (pinfunction "1_32") (pintype "passive"))
    )
    (net (code "265") (name "unconnected-(X1AG-1-Pad33)") (class "Default")
      (node (ref "X1") (pin "33") (pinfunction "1_33") (pintype "passive"))
    )
    (net (code "266") (name "unconnected-(X1AH-1-Pad34)") (class "Default")
      (node (ref "X1") (pin "34") (pinfunction "1_34") (pintype "passive"))
    )
    (net (code "267") (name "unconnected-(X1AI-1-Pad35)") (class "Default")
      (node (ref "X1") (pin "35") (pinfunction "1_35") (pintype "passive"))
    )
    (net (code "268") (name "unconnected-(X1AJ-1-Pad36)") (class "Default")
      (node (ref "X1") (pin "36") (pinfunction "1_36") (pintype "passive"))
    )
    (net (code "269") (name "unconnected-(X1AK-1-Pad37)") (class "Default")
      (node (ref "X1") (pin "37") (pinfunction "1_37") (pintype "passive"))
    )
  )
)
